# Trackerv4.net
KiCad netlist of a schematic drawn in EAGLE
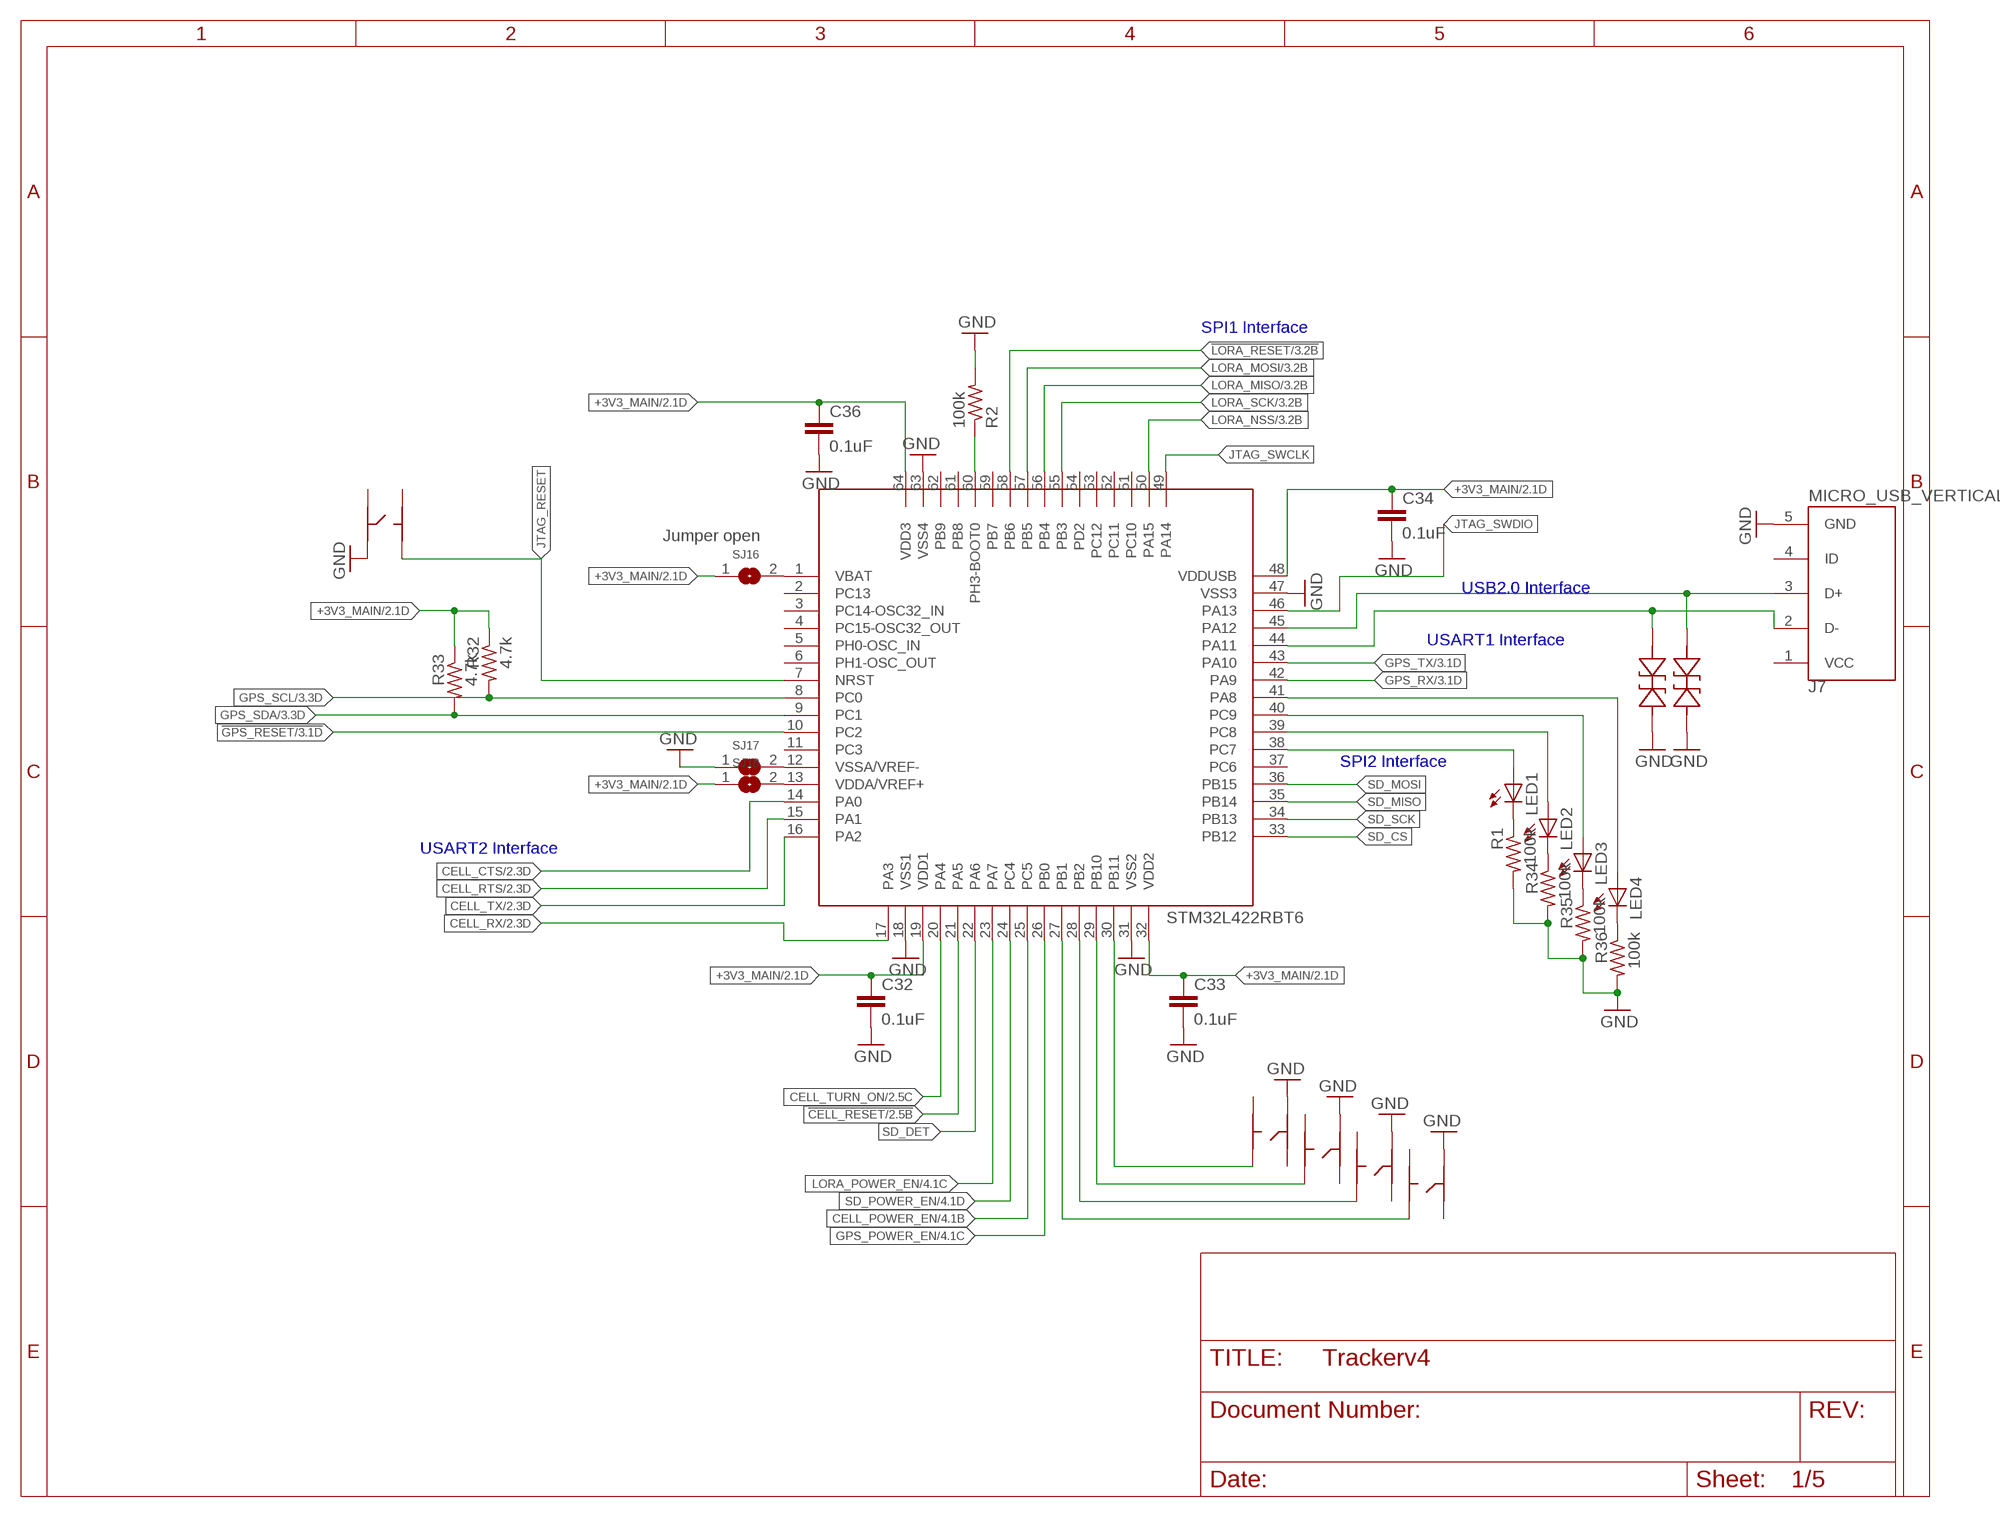
[diagram p0: schematic, sheet 1]
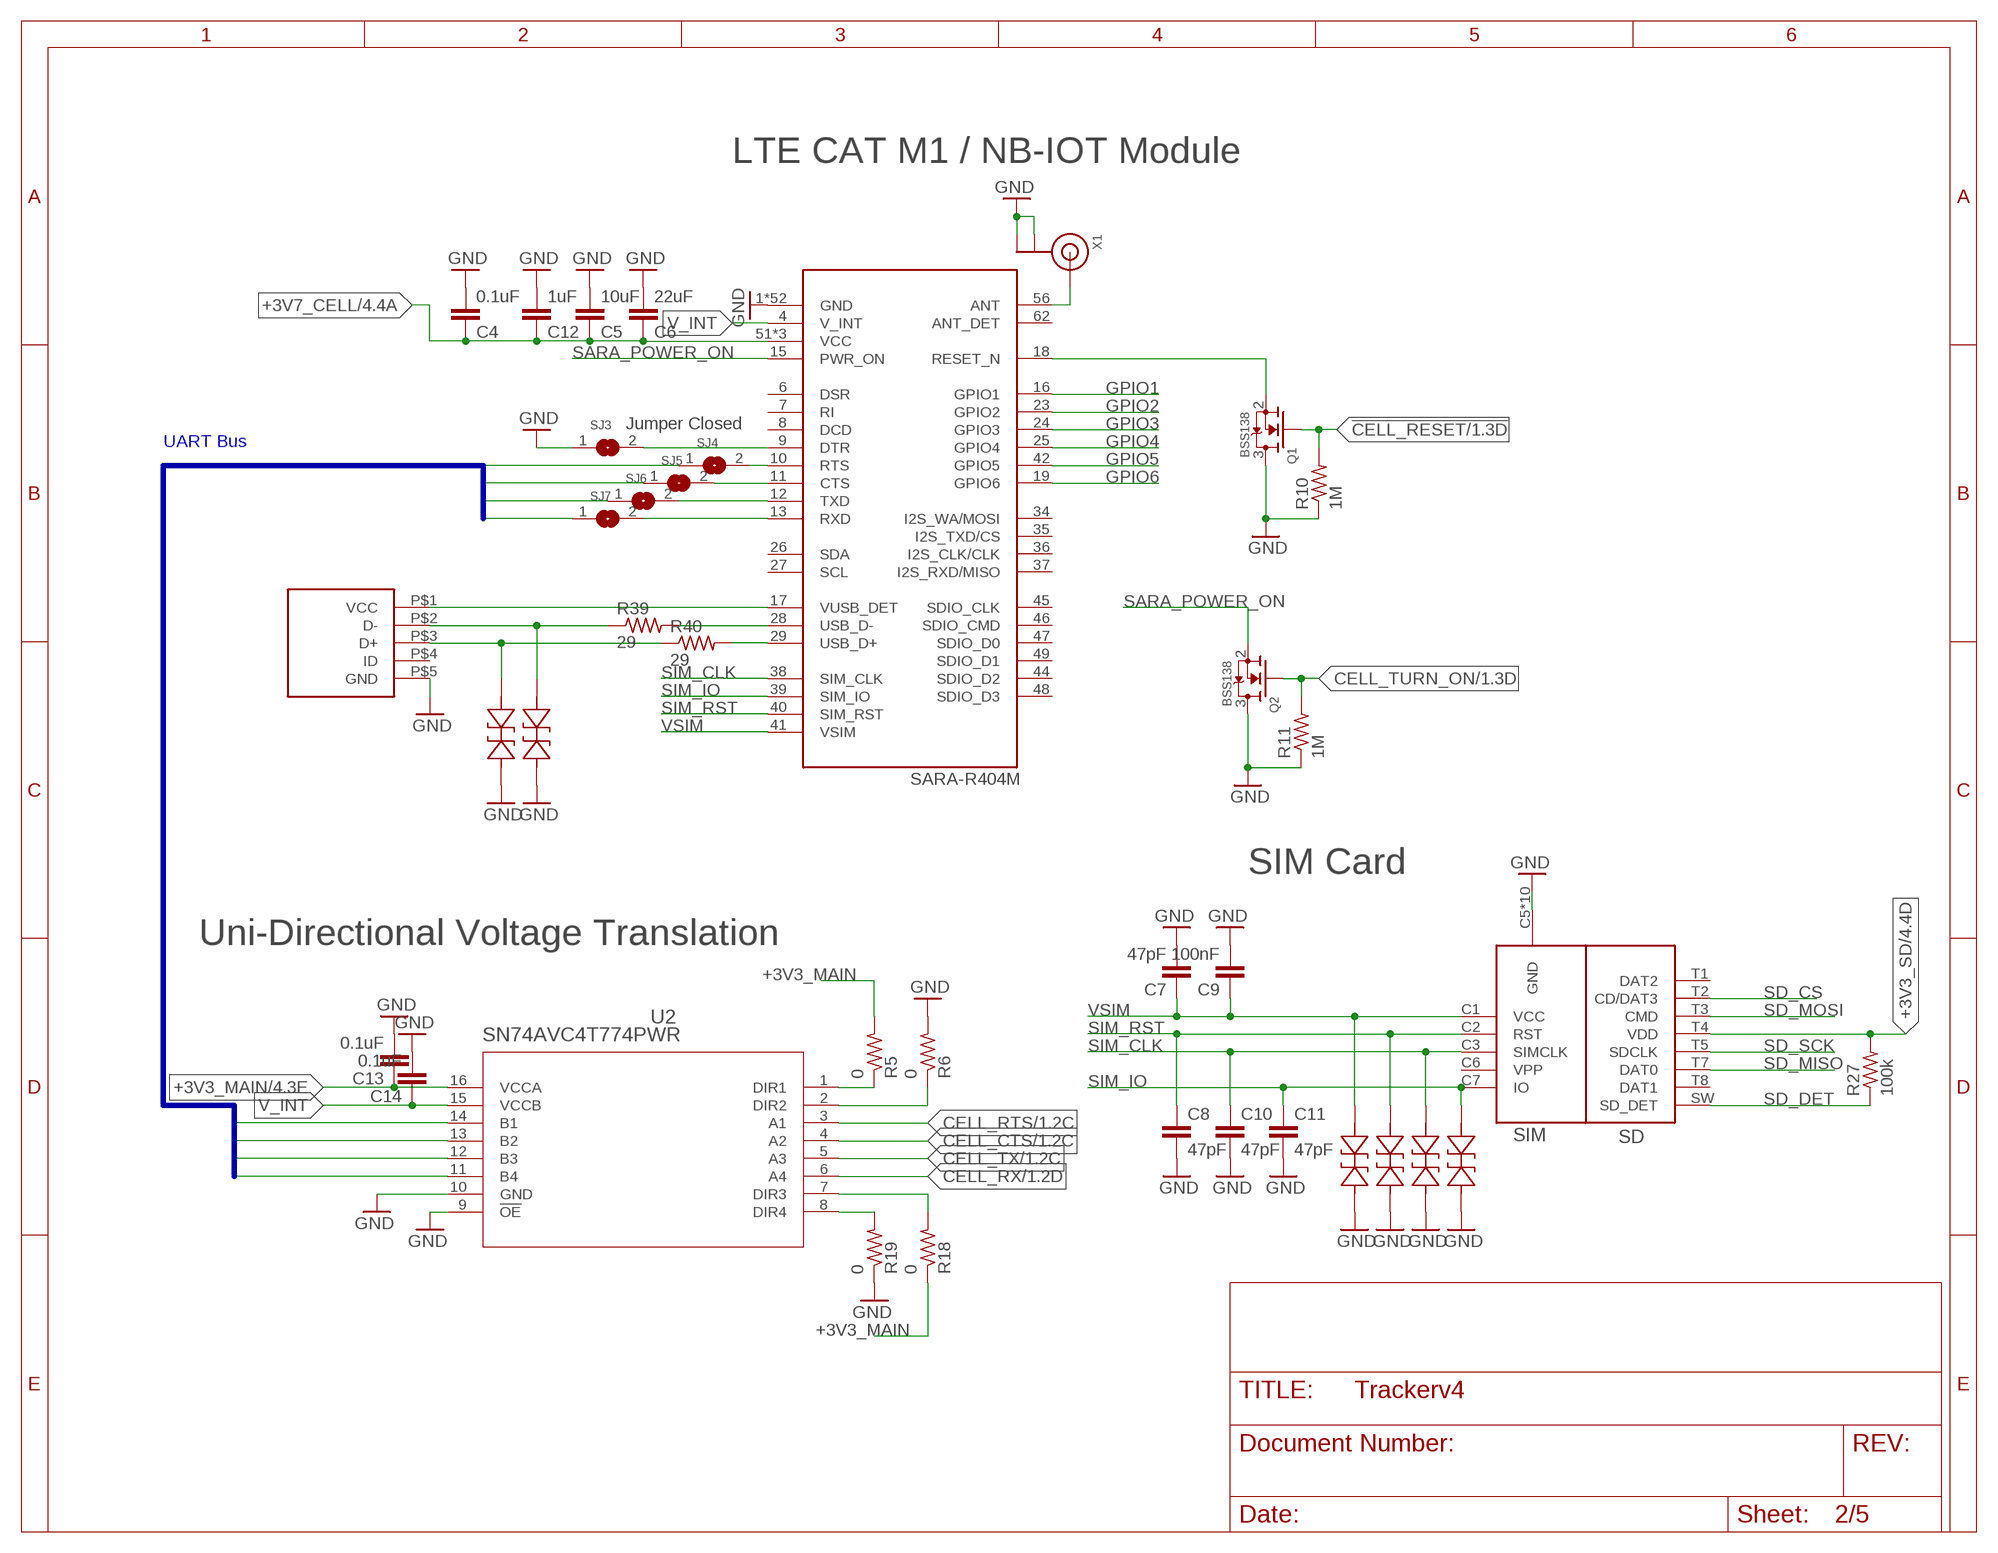
[diagram p1: schematic, sheet 2]
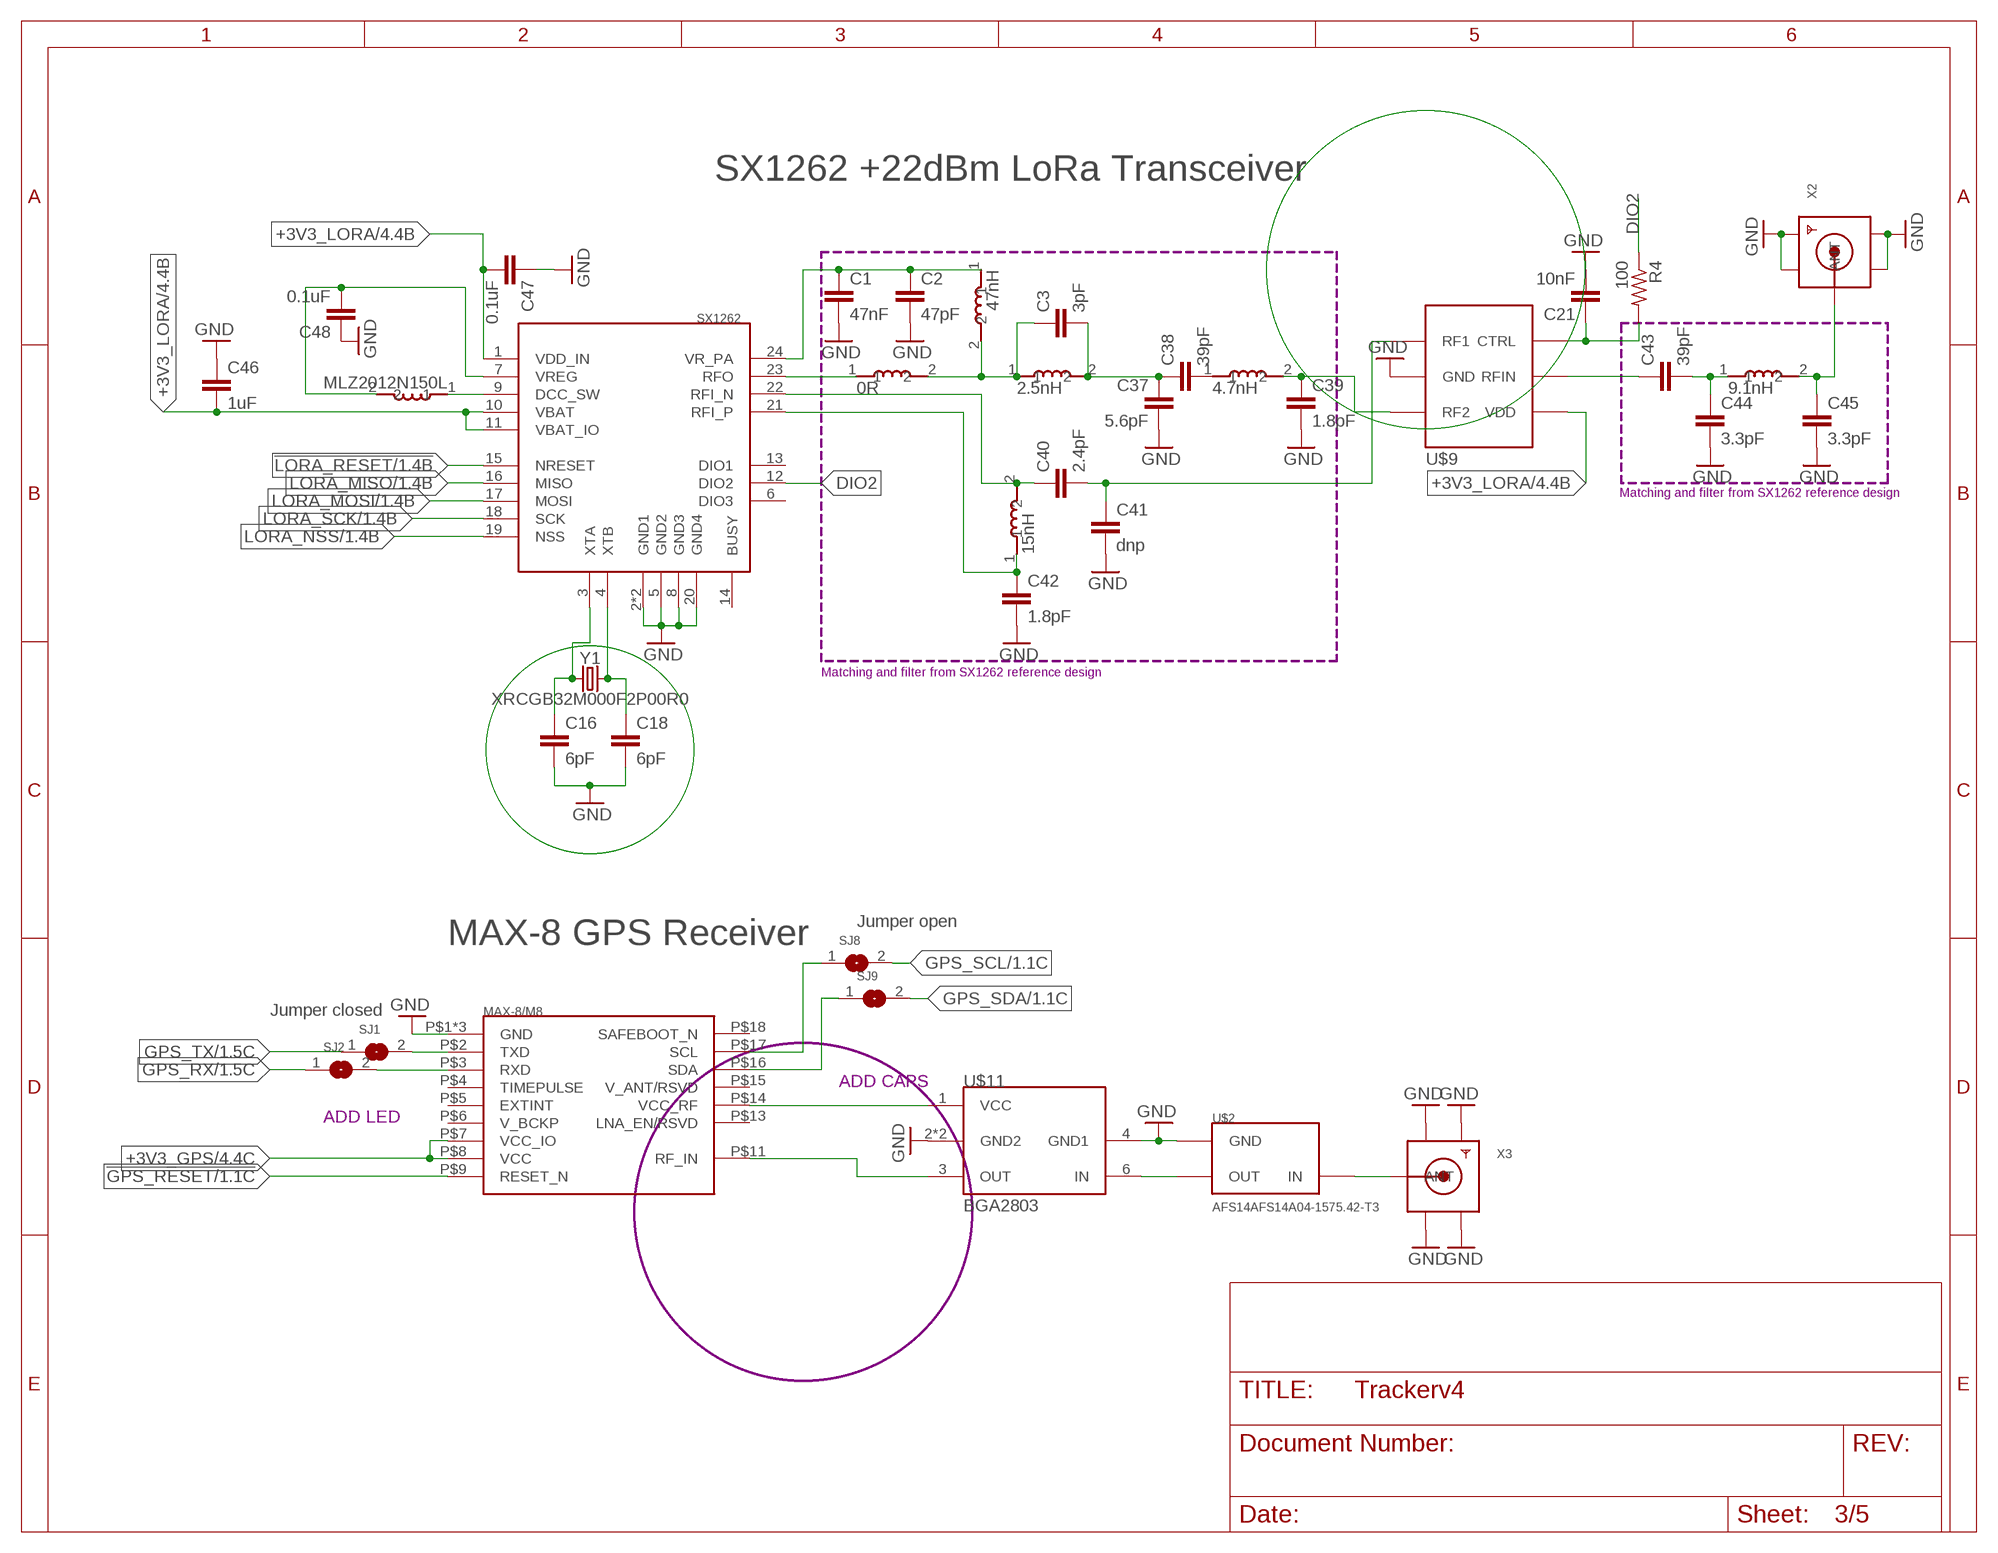
[diagram p2: schematic, sheet 3]
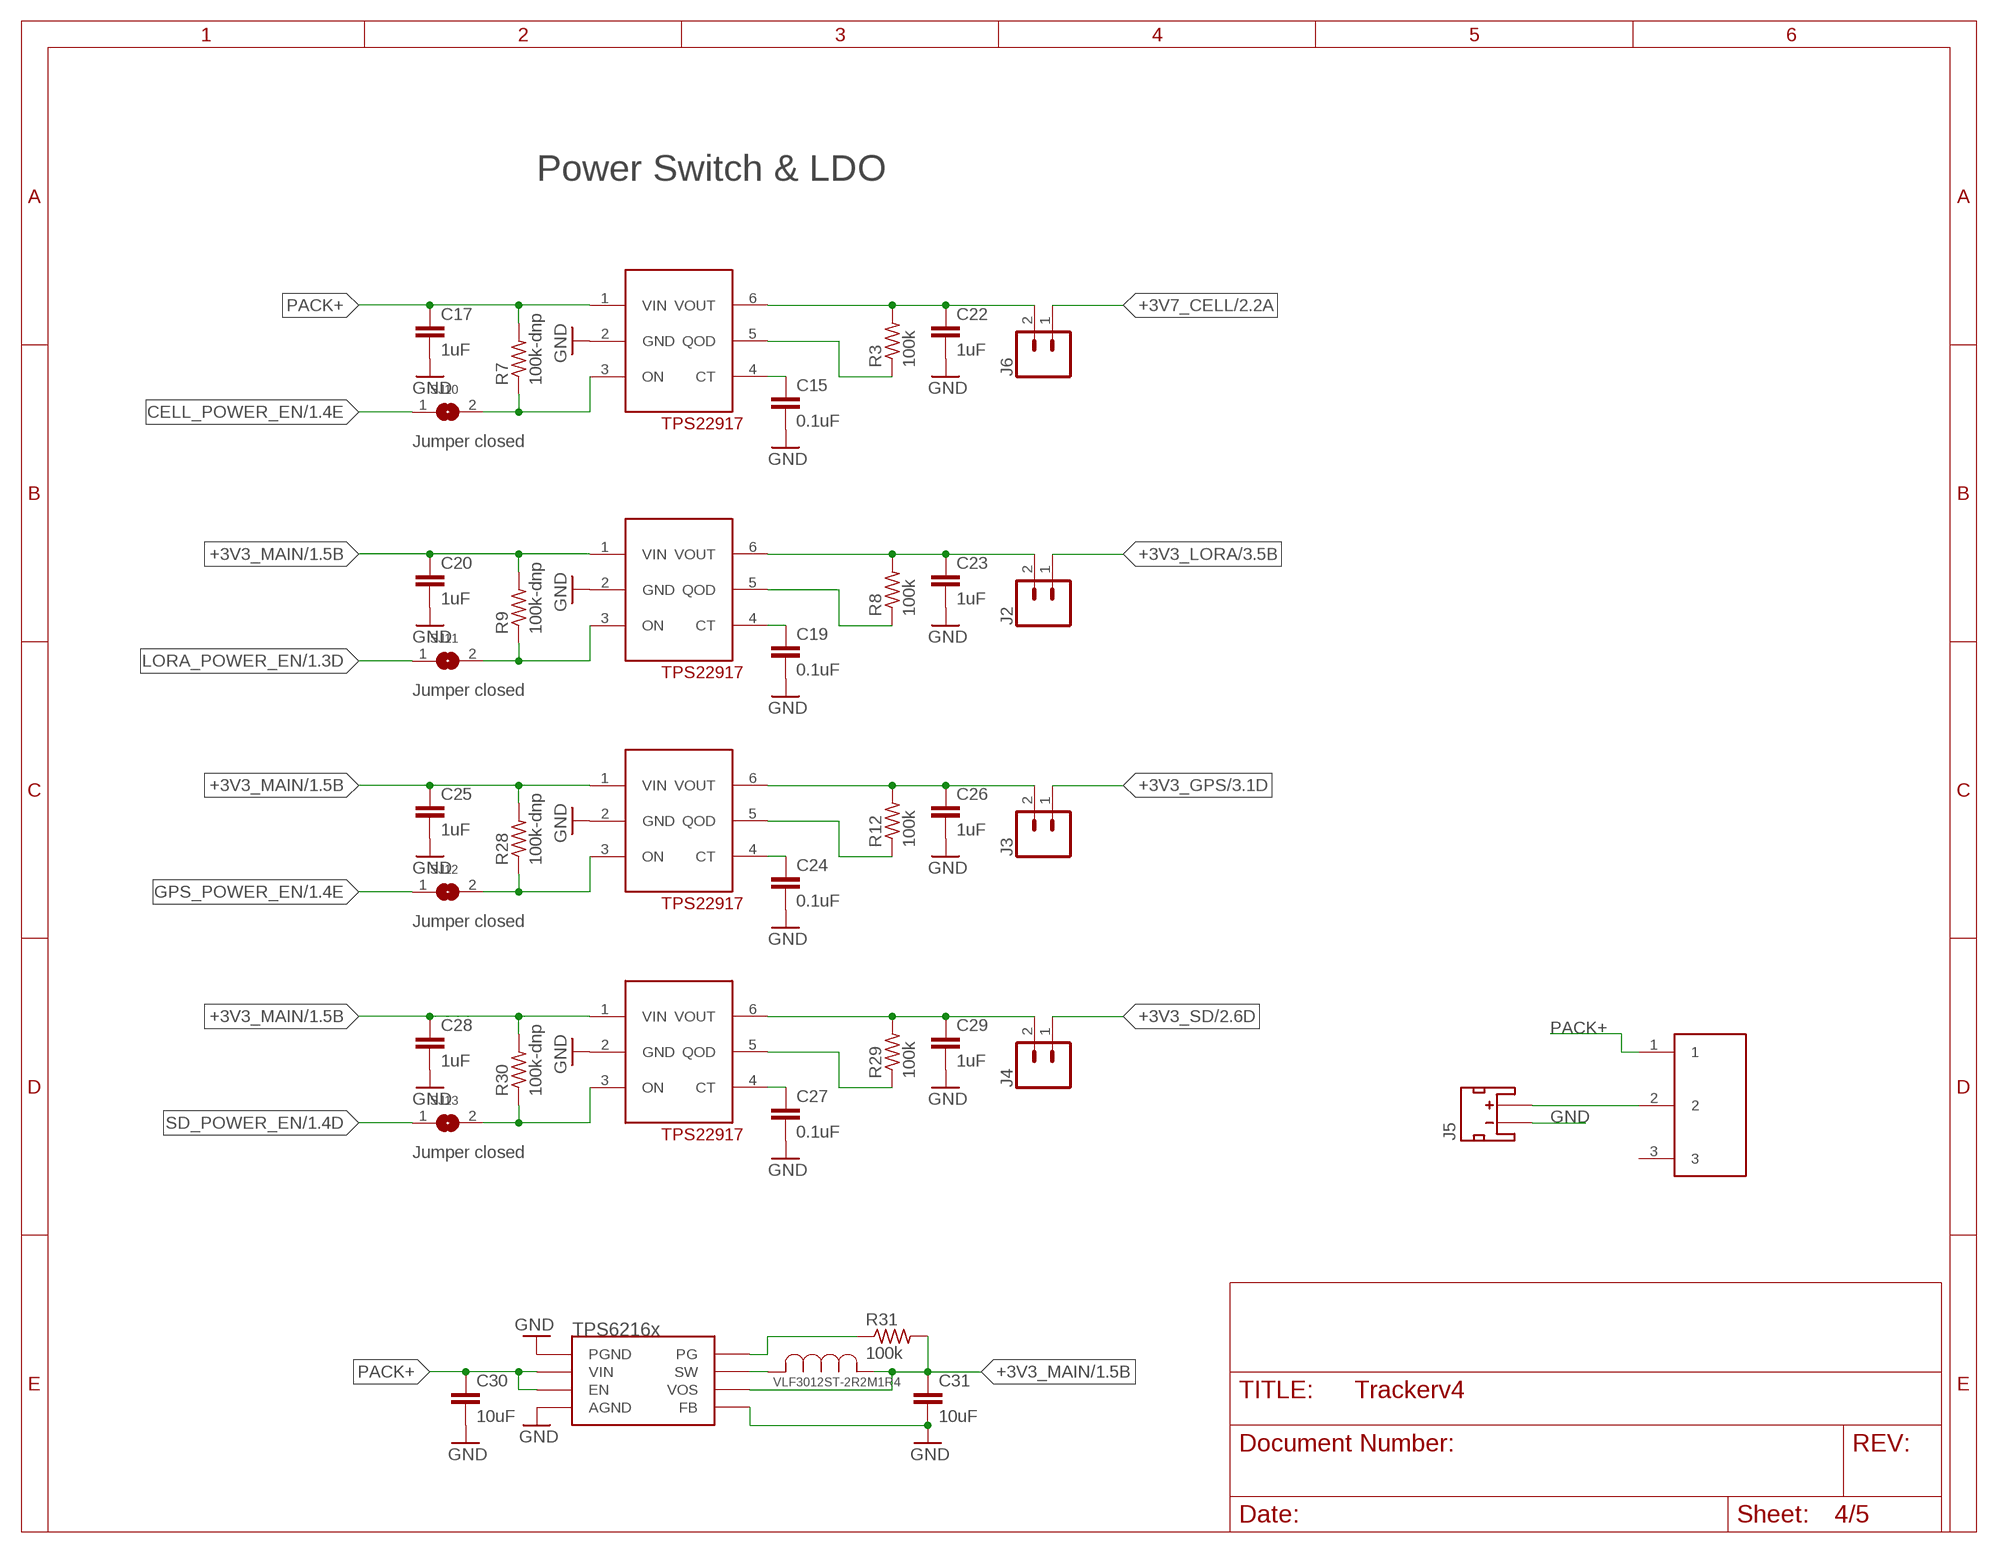
[diagram p3: schematic, sheet 4]
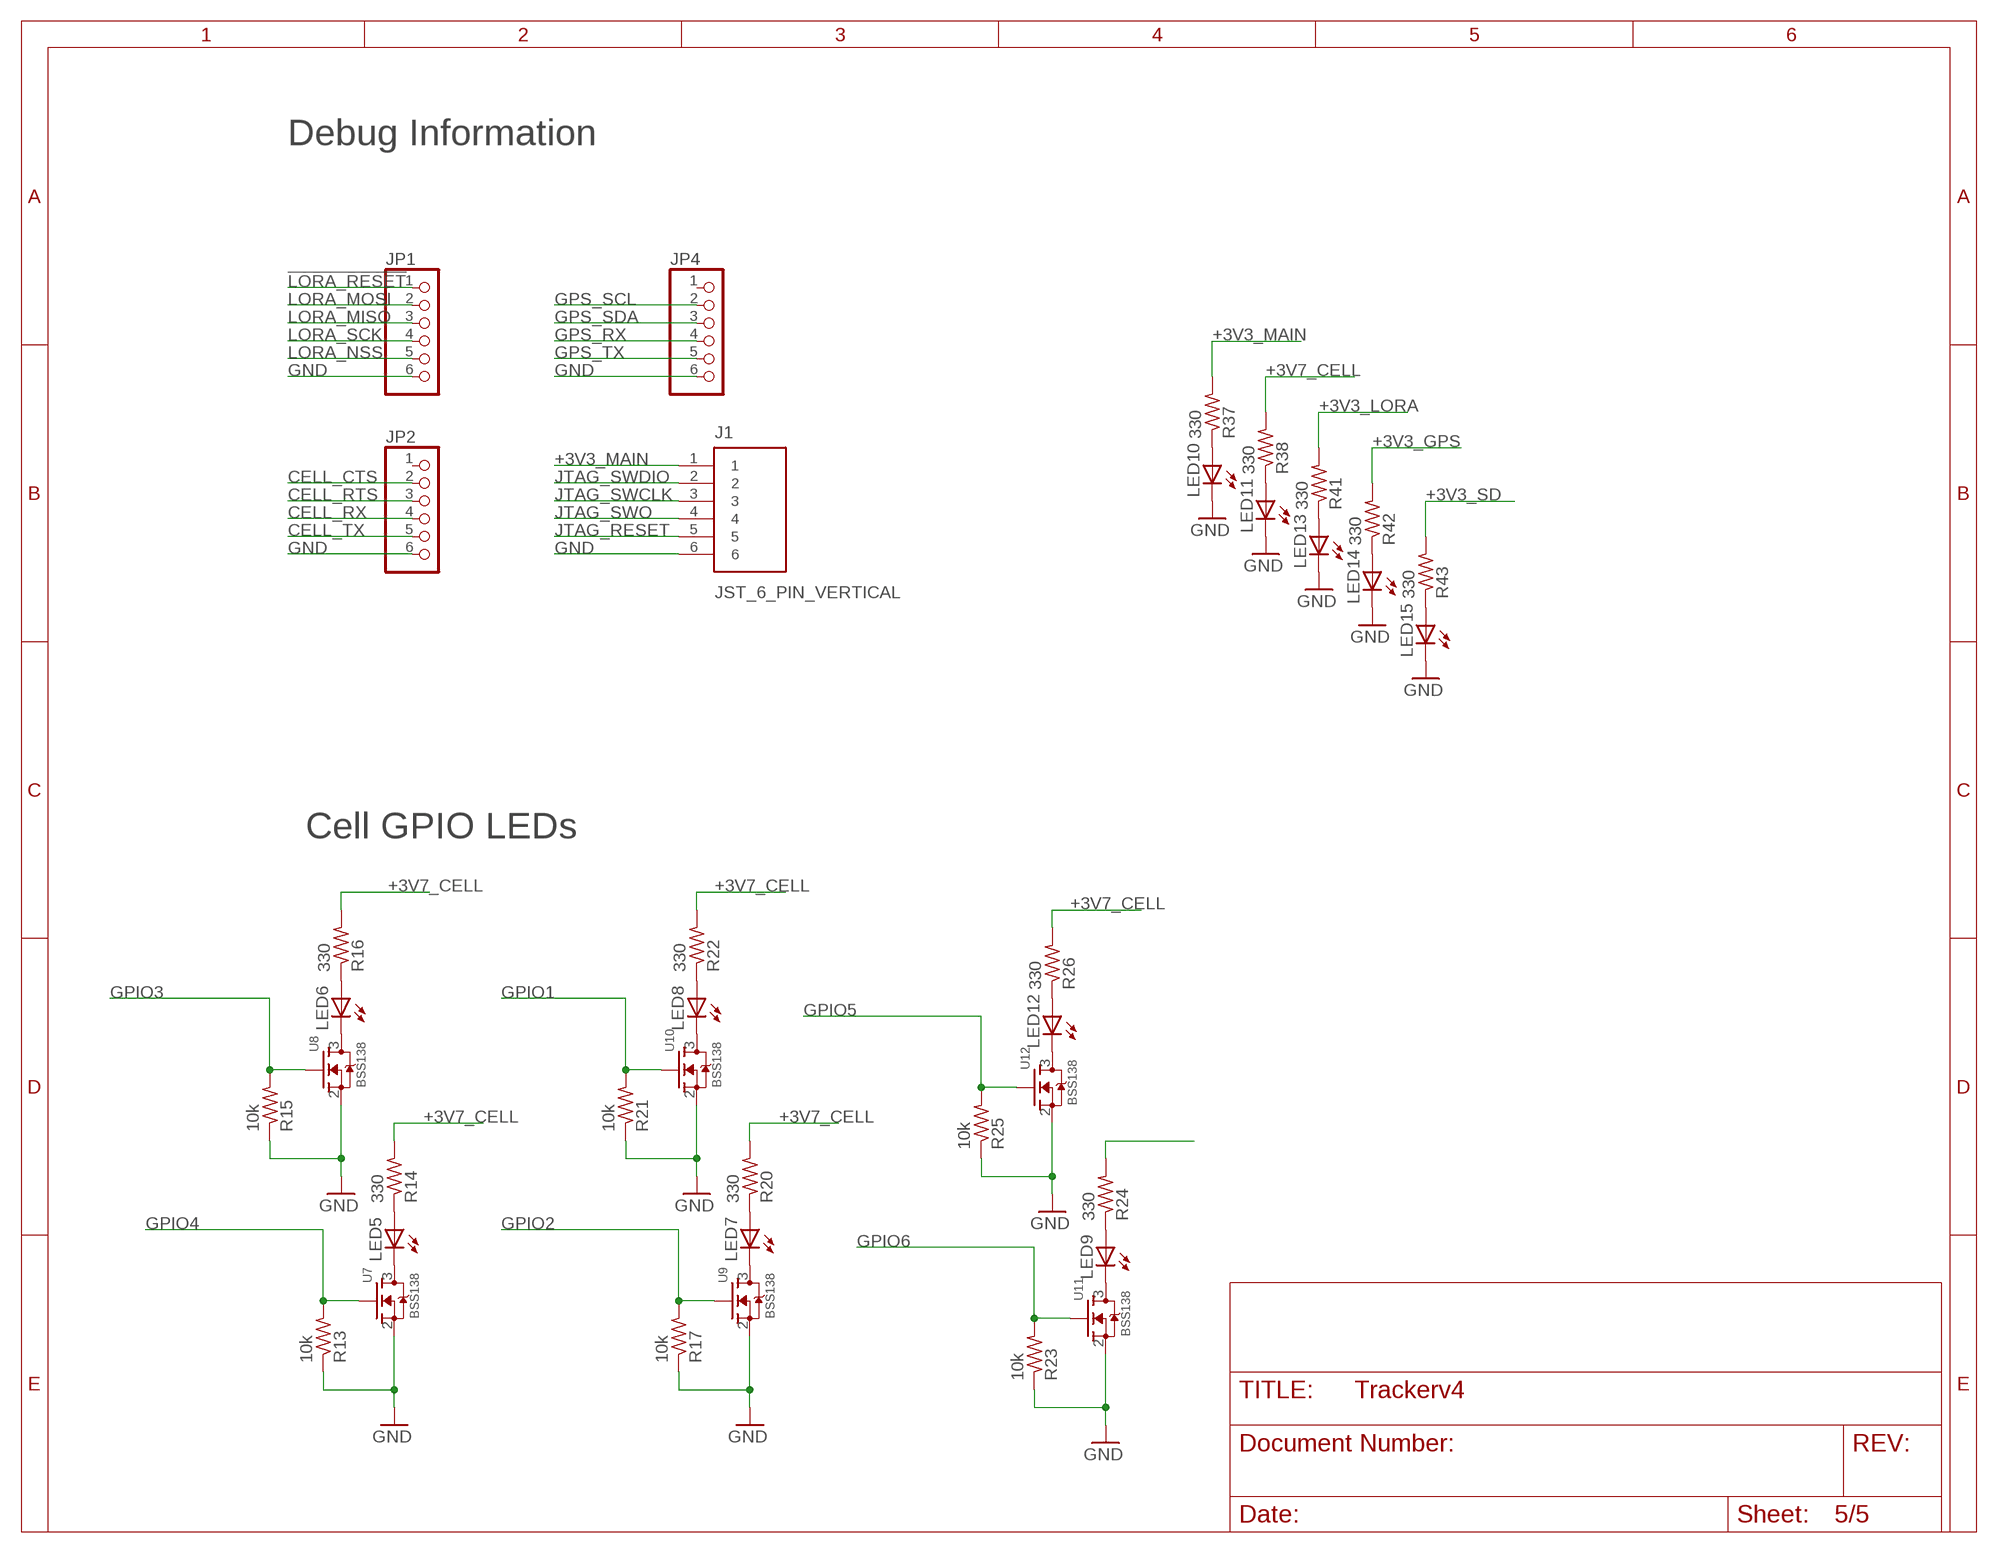
[diagram p4: schematic, sheet 5]

(export (version "E")
  (design (tool "Eeschema 10.0.6"))
  (components
    (comp (ref "J1")
      (value "JST_6_PIN_VERTICAL")
      (footprint "eagle-import:JST-6-SMD-VERT-1.0MM")
      (libsource (lib "eagle-import") (part "JST_6_PIN_VERTICAL"))
    )
    (comp (ref "JP1")
      (value "PINHD-1X6")
      (footprint "eagle-import:1X06")
      (libsource (lib "eagle-import") (part "PINHD-1X6"))
    )
    (comp (ref "JP2")
      (value "PINHD-1X6")
      (footprint "eagle-import:1X06")
      (libsource (lib "eagle-import") (part "PINHD-1X6"))
    )
    (comp (ref "JP4")
      (value "PINHD-1X6")
      (footprint "eagle-import:1X06")
      (libsource (lib "eagle-import") (part "PINHD-1X6"))
    )
    (comp (ref "LED5")
      (value "LEDCHIPLED_0603")
      (footprint "eagle-import:CHIPLED_0603")
      (libsource (lib "eagle-import") (part "LEDCHIPLED_0603"))
    )
    (comp (ref "LED6")
      (value "LEDCHIPLED_0603")
      (footprint "eagle-import:CHIPLED_0603")
      (libsource (lib "eagle-import") (part "LEDCHIPLED_0603"))
    )
    (comp (ref "LED7")
      (value "LEDCHIPLED_0603")
      (footprint "eagle-import:CHIPLED_0603")
      (libsource (lib "eagle-import") (part "LEDCHIPLED_0603"))
    )
    (comp (ref "LED8")
      (value "LEDCHIPLED_0603")
      (footprint "eagle-import:CHIPLED_0603")
      (libsource (lib "eagle-import") (part "LEDCHIPLED_0603"))
    )
    (comp (ref "LED9")
      (value "LEDCHIPLED_0603")
      (footprint "eagle-import:CHIPLED_0603")
      (libsource (lib "eagle-import") (part "LEDCHIPLED_0603"))
    )
    (comp (ref "LED10")
      (value "LEDCHIPLED_0603")
      (footprint "eagle-import:CHIPLED_0603")
      (libsource (lib "eagle-import") (part "LEDCHIPLED_0603"))
    )
    (comp (ref "LED11")
      (value "LEDCHIPLED_0603")
      (footprint "eagle-import:CHIPLED_0603")
      (libsource (lib "eagle-import") (part "LEDCHIPLED_0603"))
    )
    (comp (ref "LED12")
      (value "LEDCHIPLED_0603")
      (footprint "eagle-import:CHIPLED_0603")
      (libsource (lib "eagle-import") (part "LEDCHIPLED_0603"))
    )
    (comp (ref "LED13")
      (value "LEDCHIPLED_0603")
      (footprint "eagle-import:CHIPLED_0603")
      (libsource (lib "eagle-import") (part "LEDCHIPLED_0603"))
    )
    (comp (ref "LED14")
      (value "LEDCHIPLED_0603")
      (footprint "eagle-import:CHIPLED_0603")
      (libsource (lib "eagle-import") (part "LEDCHIPLED_0603"))
    )
    (comp (ref "LED15")
      (value "LEDCHIPLED_0603")
      (footprint "eagle-import:CHIPLED_0603")
      (libsource (lib "eagle-import") (part "LEDCHIPLED_0603"))
    )
    (comp (ref "R13")
      (value "10k")
      (footprint "eagle-import:R0402")
      (libsource (lib "eagle-import") (part "R-US_R0402"))
    )
    (comp (ref "R14")
      (value "330")
      (footprint "eagle-import:R0402")
      (libsource (lib "eagle-import") (part "R-US_R0402"))
    )
    (comp (ref "R15")
      (value "10k")
      (footprint "eagle-import:R0402")
      (libsource (lib "eagle-import") (part "R-US_R0402"))
    )
    (comp (ref "R16")
      (value "330")
      (footprint "eagle-import:R0402")
      (libsource (lib "eagle-import") (part "R-US_R0402"))
    )
    (comp (ref "R17")
      (value "10k")
      (footprint "eagle-import:R0402")
      (libsource (lib "eagle-import") (part "R-US_R0402"))
    )
    (comp (ref "R20")
      (value "330")
      (footprint "eagle-import:R0402")
      (libsource (lib "eagle-import") (part "R-US_R0402"))
    )
    (comp (ref "R21")
      (value "10k")
      (footprint "eagle-import:R0402")
      (libsource (lib "eagle-import") (part "R-US_R0402"))
    )
    (comp (ref "R22")
      (value "330")
      (footprint "eagle-import:R0402")
      (libsource (lib "eagle-import") (part "R-US_R0402"))
    )
    (comp (ref "R23")
      (value "10k")
      (footprint "eagle-import:R0402")
      (libsource (lib "eagle-import") (part "R-US_R0402"))
    )
    (comp (ref "R24")
      (value "330")
      (footprint "eagle-import:R0402")
      (libsource (lib "eagle-import") (part "R-US_R0402"))
    )
    (comp (ref "R25")
      (value "10k")
      (footprint "eagle-import:R0402")
      (libsource (lib "eagle-import") (part "R-US_R0402"))
    )
    (comp (ref "R26")
      (value "330")
      (footprint "eagle-import:R0402")
      (libsource (lib "eagle-import") (part "R-US_R0402"))
    )
    (comp (ref "R37")
      (value "330")
      (footprint "eagle-import:R0402")
      (libsource (lib "eagle-import") (part "R-US_R0402"))
    )
    (comp (ref "R38")
      (value "330")
      (footprint "eagle-import:R0402")
      (libsource (lib "eagle-import") (part "R-US_R0402"))
    )
    (comp (ref "R41")
      (value "330")
      (footprint "eagle-import:R0402")
      (libsource (lib "eagle-import") (part "R-US_R0402"))
    )
    (comp (ref "R42")
      (value "330")
      (footprint "eagle-import:R0402")
      (libsource (lib "eagle-import") (part "R-US_R0402"))
    )
    (comp (ref "R43")
      (value "330")
      (footprint "eagle-import:R0402")
      (libsource (lib "eagle-import") (part "R-US_R0402"))
    )
    (comp (ref "U7")
      (value "BSS138")
      (footprint "eagle-import:SOT23-3")
      (libsource (lib "eagle-import") (part "BSS138"))
    )
    (comp (ref "U8")
      (value "BSS138")
      (footprint "eagle-import:SOT23-3")
      (libsource (lib "eagle-import") (part "BSS138"))
    )
    (comp (ref "U9")
      (value "BSS138")
      (footprint "eagle-import:SOT23-3")
      (libsource (lib "eagle-import") (part "BSS138"))
    )
    (comp (ref "U10")
      (value "BSS138")
      (footprint "eagle-import:SOT23-3")
      (libsource (lib "eagle-import") (part "BSS138"))
    )
    (comp (ref "U11")
      (value "BSS138")
      (footprint "eagle-import:SOT23-3")
      (libsource (lib "eagle-import") (part "BSS138"))
    )
    (comp (ref "U12")
      (value "BSS138")
      (footprint "eagle-import:SOT23-3")
      (libsource (lib "eagle-import") (part "BSS138"))
    )
    (comp (ref "C1")
      (value "47nF")
      (footprint "eagle-import:C0402")
      (libsource (lib "eagle-import") (part "C-EUC0402"))
    )
    (comp (ref "C2")
      (value "47pF")
      (footprint "eagle-import:C0402")
      (libsource (lib "eagle-import") (part "C-EUC0402"))
    )
    (comp (ref "C3")
      (value "3pF")
      (footprint "eagle-import:C0402")
      (libsource (lib "eagle-import") (part "C-EUC0402"))
    )
    (comp (ref "C16")
      (value "6pF")
      (footprint "eagle-import:C0402")
      (libsource (lib "eagle-import") (part "C-EUC0402"))
    )
    (comp (ref "C18")
      (value "6pF")
      (footprint "eagle-import:C0402")
      (libsource (lib "eagle-import") (part "C-EUC0402"))
    )
    (comp (ref "C21")
      (value "10nF")
      (footprint "eagle-import:C0402")
      (libsource (lib "eagle-import") (part "C-EUC0402"))
    )
    (comp (ref "C37")
      (value "5.6pF")
      (footprint "eagle-import:C0402")
      (libsource (lib "eagle-import") (part "C-EUC0402"))
    )
    (comp (ref "C38")
      (value "39pF")
      (footprint "eagle-import:C0402")
      (libsource (lib "eagle-import") (part "C-EUC0402"))
    )
    (comp (ref "C39")
      (value "1.8pF")
      (footprint "eagle-import:C0402")
      (libsource (lib "eagle-import") (part "C-EUC0402"))
    )
    (comp (ref "C40")
      (value "2.4pF")
      (footprint "eagle-import:C0402")
      (libsource (lib "eagle-import") (part "C-EUC0402"))
    )
    (comp (ref "C41")
      (value "dnp")
      (footprint "eagle-import:C0402")
      (libsource (lib "eagle-import") (part "C-EUC0402"))
    )
    (comp (ref "C42")
      (value "1.8pF")
      (footprint "eagle-import:C0402")
      (libsource (lib "eagle-import") (part "C-EUC0402"))
    )
    (comp (ref "C43")
      (value "39pF")
      (footprint "eagle-import:C0402")
      (libsource (lib "eagle-import") (part "C-EUC0402"))
    )
    (comp (ref "C44")
      (value "3.3pF")
      (footprint "eagle-import:C0402")
      (libsource (lib "eagle-import") (part "C-EUC0402"))
    )
    (comp (ref "C45")
      (value "3.3pF")
      (footprint "eagle-import:C0402")
      (libsource (lib "eagle-import") (part "C-EUC0402"))
    )
    (comp (ref "C46")
      (value "1uF")
      (footprint "eagle-import:C0603")
      (libsource (lib "eagle-import") (part "C-EUC0603"))
    )
    (comp (ref "C47")
      (value "0.1uF")
      (footprint "eagle-import:C0402")
      (libsource (lib "eagle-import") (part "C-EUC0402"))
    )
    (comp (ref "C48")
      (value "0.1uF")
      (footprint "eagle-import:C0402")
      (libsource (lib "eagle-import") (part "C-EUC0402"))
    )
    (comp (ref "R4")
      (value "100")
      (footprint "eagle-import:R0402")
      (libsource (lib "eagle-import") (part "R-US_R0402"))
    )
    (comp (ref "SJ1")
      (value "SOLDERJUMPERCLOSED")
      (footprint "eagle-import:SOLDERJUMPER_CLOSEDWIRE")
      (libsource (lib "eagle-import") (part "SOLDERJUMPERCLOSED"))
    )
    (comp (ref "SJ2")
      (value "SOLDERJUMPERCLOSED")
      (footprint "eagle-import:SOLDERJUMPER_CLOSEDWIRE")
      (libsource (lib "eagle-import") (part "SOLDERJUMPERCLOSED"))
    )
    (comp (ref "SJ8")
      (value "SOLDERJUMPERREFLOW")
      (footprint "eagle-import:SOLDERJUMPER_REFLOW")
      (libsource (lib "eagle-import") (part "SOLDERJUMPERREFLOW"))
    )
    (comp (ref "SJ9")
      (value "SOLDERJUMPERREFLOW")
      (footprint "eagle-import:SOLDERJUMPER_REFLOW")
      (libsource (lib "eagle-import") (part "SOLDERJUMPERREFLOW"))
    )
    (comp (ref "U$2")
      (value "AFS14AFS14A04-1575.42-T3")
      (footprint "eagle-import:AFS14")
      (libsource (lib "eagle-import") (part "AFS14AFS14A04-1575.42-T3"))
    )
    (comp (ref "U$3")
      (value "MLZ2012N150L")
      (footprint "eagle-import:C0805")
      (libsource (lib "eagle-import") (part "INDUCTOR0805"))
    )
    (comp (ref "U$7")
      (value "SX1262")
      (footprint "eagle-import:QFN50P400X400X100-25T260")
      (libsource (lib "eagle-import") (part "SX1262"))
    )
    (comp (ref "U$8")
      (value "MAX-8/M8")
      (footprint "eagle-import:MAX-8-M8")
      (libsource (lib "eagle-import") (part "MAX-8/M8"))
    )
    (comp (ref "U$9")
      (value "BGS12SN6E6327XTSA1")
      (footprint "eagle-import:TSNP-6-8")
      (libsource (lib "eagle-import") (part "BGS12SN6E6327XTSA1"))
    )
    (comp (ref "U$10")
      (value "47nH")
      (footprint "eagle-import:0402")
      (libsource (lib "eagle-import") (part "INDUCTOR0402"))
    )
    (comp (ref "U$11")
      (value "BGA2803")
      (footprint "eagle-import:SOT363_6SOIC")
      (libsource (lib "eagle-import") (part "BGA2803"))
    )
    (comp (ref "U$12")
      (value "2.5nH")
      (footprint "eagle-import:0402")
      (libsource (lib "eagle-import") (part "INDUCTOR0402"))
    )
    (comp (ref "U$13")
      (value "4.7nH")
      (footprint "eagle-import:0402")
      (libsource (lib "eagle-import") (part "INDUCTOR0402"))
    )
    (comp (ref "U$14")
      (value "15nH")
      (footprint "eagle-import:0402")
      (libsource (lib "eagle-import") (part "INDUCTOR0402"))
    )
    (comp (ref "U$15")
      (value "9.1nH")
      (footprint "eagle-import:0402")
      (libsource (lib "eagle-import") (part "INDUCTOR0402"))
    )
    (comp (ref "U$16")
      (value "0R")
      (footprint "eagle-import:0402")
      (libsource (lib "eagle-import") (part "INDUCTOR0402"))
    )
    (comp (ref "X2")
      (value "SMACONNECTOR_EDGE")
      (footprint "eagle-import:SMA_EDGELAUNCH")
      (libsource (lib "eagle-import") (part "SMACONNECTOR_EDGE"))
    )
    (comp (ref "X3")
      (value "SMACONNECTOR_EDGE_UFL")
      (footprint "eagle-import:SMA_EDGELAUNCH_UFL")
      (libsource (lib "eagle-import") (part "SMACONNECTOR_EDGE_UFL"))
    )
    (comp (ref "Y1")
      (value "XRCGB32M000F2P00R0")
      (footprint "eagle-import:CRYSTAL-SMD-2.0X1.6MM")
      (libsource (lib "eagle-import") (part "CRYSTAL-32MHZ-SMD-2.0X1.6MM"))
    )
    (comp (ref "C15")
      (value "0.1uF")
      (footprint "eagle-import:C0402")
      (libsource (lib "eagle-import") (part "C-EUC0402"))
    )
    (comp (ref "C17")
      (value "1uF")
      (footprint "eagle-import:C0402")
      (libsource (lib "eagle-import") (part "C-EUC0402"))
    )
    (comp (ref "C19")
      (value "0.1uF")
      (footprint "eagle-import:C0402")
      (libsource (lib "eagle-import") (part "C-EUC0402"))
    )
    (comp (ref "C20")
      (value "1uF")
      (footprint "eagle-import:C0402")
      (libsource (lib "eagle-import") (part "C-EUC0402"))
    )
    (comp (ref "C22")
      (value "1uF")
      (footprint "eagle-import:C0402")
      (libsource (lib "eagle-import") (part "C-EUC0402"))
    )
    (comp (ref "C23")
      (value "1uF")
      (footprint "eagle-import:C0402")
      (libsource (lib "eagle-import") (part "C-EUC0402"))
    )
    (comp (ref "C24")
      (value "0.1uF")
      (footprint "eagle-import:C0402")
      (libsource (lib "eagle-import") (part "C-EUC0402"))
    )
    (comp (ref "C25")
      (value "1uF")
      (footprint "eagle-import:C0402")
      (libsource (lib "eagle-import") (part "C-EUC0402"))
    )
    (comp (ref "C26")
      (value "1uF")
      (footprint "eagle-import:C0402")
      (libsource (lib "eagle-import") (part "C-EUC0402"))
    )
    (comp (ref "C27")
      (value "0.1uF")
      (footprint "eagle-import:C0402")
      (libsource (lib "eagle-import") (part "C-EUC0402"))
    )
    (comp (ref "C28")
      (value "1uF")
      (footprint "eagle-import:C0402")
      (libsource (lib "eagle-import") (part "C-EUC0402"))
    )
    (comp (ref "C29")
      (value "1uF")
      (footprint "eagle-import:C0402")
      (libsource (lib "eagle-import") (part "C-EUC0402"))
    )
    (comp (ref "C30")
      (value "10uF")
      (footprint "eagle-import:C0805")
      (libsource (lib "eagle-import") (part "C-EUC0805"))
    )
    (comp (ref "C31")
      (value "10uF")
      (footprint "eagle-import:C0805")
      (libsource (lib "eagle-import") (part "C-EUC0805"))
    )
    (comp (ref "J2")
      (value "CONN_02")
      (footprint "eagle-import:1X02")
      (libsource (lib "eagle-import") (part "CONN_02"))
    )
    (comp (ref "J3")
      (value "CONN_02")
      (footprint "eagle-import:1X02")
      (libsource (lib "eagle-import") (part "CONN_02"))
    )
    (comp (ref "J4")
      (value "CONN_02")
      (footprint "eagle-import:1X02")
      (libsource (lib "eagle-import") (part "CONN_02"))
    )
    (comp (ref "J5")
      (value "JST_2MM_MALE")
      (footprint "eagle-import:JST-2-SMD")
      (libsource (lib "eagle-import") (part "JST_2MM_MALE"))
    )
    (comp (ref "J6")
      (value "CONN_02")
      (footprint "eagle-import:1X02")
      (libsource (lib "eagle-import") (part "CONN_02"))
    )
    (comp (ref "R3")
      (value "100k")
      (footprint "eagle-import:R0402")
      (libsource (lib "eagle-import") (part "R-US_R0402"))
    )
    (comp (ref "R7")
      (value "100k-dnp")
      (footprint "eagle-import:R0402")
      (libsource (lib "eagle-import") (part "R-US_R0402"))
    )
    (comp (ref "R8")
      (value "100k")
      (footprint "eagle-import:R0402")
      (libsource (lib "eagle-import") (part "R-US_R0402"))
    )
    (comp (ref "R9")
      (value "100k-dnp")
      (footprint "eagle-import:R0402")
      (libsource (lib "eagle-import") (part "R-US_R0402"))
    )
    (comp (ref "R12")
      (value "100k")
      (footprint "eagle-import:R0402")
      (libsource (lib "eagle-import") (part "R-US_R0402"))
    )
    (comp (ref "R28")
      (value "100k-dnp")
      (footprint "eagle-import:R0402")
      (libsource (lib "eagle-import") (part "R-US_R0402"))
    )
    (comp (ref "R29")
      (value "100k")
      (footprint "eagle-import:R0402")
      (libsource (lib "eagle-import") (part "R-US_R0402"))
    )
    (comp (ref "R30")
      (value "100k-dnp")
      (footprint "eagle-import:R0402")
      (libsource (lib "eagle-import") (part "R-US_R0402"))
    )
    (comp (ref "R31")
      (value "100k")
      (footprint "eagle-import:R0402")
      (libsource (lib "eagle-import") (part "R-US_R0402"))
    )
    (comp (ref "SJ10")
      (value "SOLDERJUMPERCLOSED")
      (footprint "eagle-import:SOLDERJUMPER_CLOSEDWIRE")
      (libsource (lib "eagle-import") (part "SOLDERJUMPERCLOSED"))
    )
    (comp (ref "SJ11")
      (value "SOLDERJUMPERCLOSED")
      (footprint "eagle-import:SOLDERJUMPER_CLOSEDWIRE")
      (libsource (lib "eagle-import") (part "SOLDERJUMPERCLOSED"))
    )
    (comp (ref "SJ12")
      (value "SOLDERJUMPERCLOSED")
      (footprint "eagle-import:SOLDERJUMPER_CLOSEDWIRE")
      (libsource (lib "eagle-import") (part "SOLDERJUMPERCLOSED"))
    )
    (comp (ref "SJ13")
      (value "SOLDERJUMPERCLOSED")
      (footprint "eagle-import:SOLDERJUMPER_CLOSEDWIRE")
      (libsource (lib "eagle-import") (part "SOLDERJUMPERCLOSED"))
    )
    (comp (ref "U$4")
      (value "VLF3012ST-2R2M1R4")
      (footprint "eagle-import:IND_3010")
      (libsource (lib "eagle-import") (part "VLF3012ST-2R2M1R4"))
    )
    (comp (ref "U$17")
      (value "SPDT_THRU")
      (footprint "eagle-import:SPDT_THRU")
      (libsource (lib "eagle-import") (part "SPDT_THRU"))
    )
    (comp (ref "U1")
      (value "TPS22917")
      (footprint "eagle-import:SOT23-6")
      (libsource (lib "eagle-import") (part "TPS22917"))
    )
    (comp (ref "U3")
      (value "TPS22917")
      (footprint "eagle-import:SOT23-6")
      (libsource (lib "eagle-import") (part "TPS22917"))
    )
    (comp (ref "U4")
      (value "TPS22917")
      (footprint "eagle-import:SOT23-6")
      (libsource (lib "eagle-import") (part "TPS22917"))
    )
    (comp (ref "U5")
      (value "TPS22917")
      (footprint "eagle-import:SOT23-6")
      (libsource (lib "eagle-import") (part "TPS22917"))
    )
    (comp (ref "U14")
      (value "TPS6216X")
      (footprint "eagle-import:8WSON")
      (libsource (lib "eagle-import") (part "TPS6216X"))
    )
    (comp (ref "C4")
      (value "0.1uF")
      (footprint "eagle-import:C0402")
      (libsource (lib "eagle-import") (part "C-EUC0402"))
    )
    (comp (ref "C5")
      (value "10uF")
      (footprint "eagle-import:C0603")
      (libsource (lib "eagle-import") (part "C-EUC0603"))
    )
    (comp (ref "C6")
      (value "22uF")
      (footprint "eagle-import:C0805")
      (libsource (lib "eagle-import") (part "C-EUC0805"))
    )
    (comp (ref "C7")
      (value "47pF")
      (footprint "eagle-import:C0402")
      (libsource (lib "eagle-import") (part "C-EUC0402"))
    )
    (comp (ref "C8")
      (value "47pF")
      (footprint "eagle-import:C0402")
      (libsource (lib "eagle-import") (part "C-EUC0402"))
    )
    (comp (ref "C9")
      (value "100nF")
      (footprint "eagle-import:C0402")
      (libsource (lib "eagle-import") (part "C-EUC0402"))
    )
    (comp (ref "C10")
      (value "47pF")
      (footprint "eagle-import:C0402")
      (libsource (lib "eagle-import") (part "C-EUC0402"))
    )
    (comp (ref "C11")
      (value "47pF")
      (footprint "eagle-import:C0402")
      (libsource (lib "eagle-import") (part "C-EUC0402"))
    )
    (comp (ref "C12")
      (value "1uF")
      (footprint "eagle-import:C0402")
      (libsource (lib "eagle-import") (part "C-EUC0402"))
    )
    (comp (ref "C13")
      (value "0.1uF")
      (footprint "eagle-import:C0402")
      (libsource (lib "eagle-import") (part "C-EUC0402"))
    )
    (comp (ref "C14")
      (value "0.1uF")
      (footprint "eagle-import:C0402")
      (libsource (lib "eagle-import") (part "C-EUC0402"))
    )
    (comp (ref "CR1")
      (value "PESD0402-140")
      (footprint "eagle-import:PESD0402")
      (fields (field (name "MANUFACTURER_PART_NUMBER") "PESD0402140"))
      (libsource (lib "eagle-import") (part "PESD0402-140"))
    )
    (comp (ref "CR2")
      (value "PESD0402-140")
      (footprint "eagle-import:PESD0402")
      (fields (field (name "MANUFACTURER_PART_NUMBER") "PESD0402140"))
      (libsource (lib "eagle-import") (part "PESD0402-140"))
    )
    (comp (ref "CR3")
      (value "PESD0402-140")
      (footprint "eagle-import:PESD0402")
      (fields (field (name "MANUFACTURER_PART_NUMBER") "PESD0402140"))
      (libsource (lib "eagle-import") (part "PESD0402-140"))
    )
    (comp (ref "CR4")
      (value "PESD0402-140")
      (footprint "eagle-import:PESD0402")
      (fields (field (name "MANUFACTURER_PART_NUMBER") "PESD0402140"))
      (libsource (lib "eagle-import") (part "PESD0402-140"))
    )
    (comp (ref "CR5")
      (value "PESD0402-140")
      (footprint "eagle-import:PESD0402")
      (fields (field (name "MANUFACTURER_PART_NUMBER") "PESD0402140"))
      (libsource (lib "eagle-import") (part "PESD0402-140"))
    )
    (comp (ref "CR6")
      (value "PESD0402-140")
      (footprint "eagle-import:PESD0402")
      (fields (field (name "MANUFACTURER_PART_NUMBER") "PESD0402140"))
      (libsource (lib "eagle-import") (part "PESD0402-140"))
    )
    (comp (ref "Q1")
      (value "BSS138")
      (footprint "eagle-import:SOT23-3")
      (libsource (lib "eagle-import") (part "BSS138"))
    )
    (comp (ref "Q2")
      (value "BSS138")
      (footprint "eagle-import:SOT23-3")
      (libsource (lib "eagle-import") (part "BSS138"))
    )
    (comp (ref "R5")
      (value "0")
      (footprint "eagle-import:R0402")
      (libsource (lib "eagle-import") (part "R-US_R0402"))
    )
    (comp (ref "R6")
      (value "0")
      (footprint "eagle-import:R0402")
      (libsource (lib "eagle-import") (part "R-US_R0402"))
    )
    (comp (ref "R10")
      (value "1M")
      (footprint "eagle-import:R0402")
      (libsource (lib "eagle-import") (part "R-US_R0402"))
    )
    (comp (ref "R11")
      (value "1M")
      (footprint "eagle-import:R0402")
      (libsource (lib "eagle-import") (part "R-US_R0402"))
    )
    (comp (ref "R18")
      (value "0")
      (footprint "eagle-import:R0402")
      (libsource (lib "eagle-import") (part "R-US_R0402"))
    )
    (comp (ref "R19")
      (value "0")
      (footprint "eagle-import:R0402")
      (libsource (lib "eagle-import") (part "R-US_R0402"))
    )
    (comp (ref "R27")
      (value "100k")
      (footprint "eagle-import:R0402")
      (libsource (lib "eagle-import") (part "R-US_R0402"))
    )
    (comp (ref "R39")
      (value "29")
      (footprint "eagle-import:R0402")
      (libsource (lib "eagle-import") (part "R-US_R0402"))
    )
    (comp (ref "R40")
      (value "29")
      (footprint "eagle-import:R0402")
      (libsource (lib "eagle-import") (part "R-US_R0402"))
    )
    (comp (ref "SJ3")
      (value "SOLDERJUMPERCLOSED")
      (footprint "eagle-import:SOLDERJUMPER_CLOSEDWIRE")
      (libsource (lib "eagle-import") (part "Charles_10020430_SOLDERJUMPERCLOSED"))
    )
    (comp (ref "SJ4")
      (value "SOLDERJUMPERCLOSED")
      (footprint "eagle-import:SOLDERJUMPER_CLOSEDWIRE")
      (libsource (lib "eagle-import") (part "Charles_10020430_SOLDERJUMPERCLOSED"))
    )
    (comp (ref "SJ5")
      (value "SOLDERJUMPERCLOSED")
      (footprint "eagle-import:SOLDERJUMPER_CLOSEDWIRE")
      (libsource (lib "eagle-import") (part "Charles_10020430_SOLDERJUMPERCLOSED"))
    )
    (comp (ref "SJ6")
      (value "SOLDERJUMPERCLOSED")
      (footprint "eagle-import:SOLDERJUMPER_CLOSEDWIRE")
      (libsource (lib "eagle-import") (part "Charles_10020430_SOLDERJUMPERCLOSED"))
    )
    (comp (ref "SJ7")
      (value "SOLDERJUMPERCLOSED")
      (footprint "eagle-import:SOLDERJUMPER_CLOSEDWIRE")
      (libsource (lib "eagle-import") (part "Charles_10020430_SOLDERJUMPERCLOSED"))
    )
    (comp (ref "U$5")
      (value "SIM_SD_MOLEX")
      (footprint "eagle-import:SIM_SD_MOLEX")
      (libsource (lib "eagle-import") (part "SIM_SD_MOLEX"))
    )
    (comp (ref "U$6")
      (value "MICRO_USB")
      (footprint "eagle-import:MOLEX_USB")
      (libsource (lib "eagle-import") (part "MICRO_USB"))
    )
    (comp (ref "U2")
      (value "SN74AVC4T774PWR")
      (footprint "eagle-import:PW16")
      (libsource (lib "eagle-import") (part "SN74AVC4T774PWR"))
    )
    (comp (ref "U6")
      (value "SARA-R404M")
      (footprint "eagle-import:SARA-R404M")
      (libsource (lib "eagle-import") (part "SARA-R404M"))
    )
    (comp (ref "X1")
      (value "ANTENNA_U.FL")
      (footprint "eagle-import:U.FL")
      (libsource (lib "eagle-import") (part "ANTENNA_U.FL"))
    )
    (comp (ref "C32")
      (value "0.1uF")
      (footprint "eagle-import:C0402")
      (libsource (lib "eagle-import") (part "C-EUC0402"))
    )
    (comp (ref "C33")
      (value "0.1uF")
      (footprint "eagle-import:C0402")
      (libsource (lib "eagle-import") (part "C-EUC0402"))
    )
    (comp (ref "C34")
      (value "0.1uF")
      (footprint "eagle-import:C0402")
      (libsource (lib "eagle-import") (part "C-EUC0402"))
    )
    (comp (ref "C36")
      (value "0.1uF")
      (footprint "eagle-import:C0402")
      (libsource (lib "eagle-import") (part "C-EUC0402"))
    )
    (comp (ref "CR7")
      (value "PESD0402-140")
      (footprint "eagle-import:PESD0402")
      (fields (field (name "MANUFACTURER_PART_NUMBER") "PESD0402140"))
      (libsource (lib "eagle-import") (part "PESD0402-140"))
    )
    (comp (ref "CR8")
      (value "PESD0402-140")
      (footprint "eagle-import:PESD0402")
      (fields (field (name "MANUFACTURER_PART_NUMBER") "PESD0402140"))
      (libsource (lib "eagle-import") (part "PESD0402-140"))
    )
    (comp (ref "J7")
      (value "MICRO_USB_VERTICAL")
      (footprint "eagle-import:MICRO_USB_VERTICAL")
      (libsource (lib "eagle-import") (part "MICRO_USB_VERTICAL"))
    )
    (comp (ref "LED1")
      (value "LEDCHIP-LED0603")
      (footprint "eagle-import:CHIP-LED0603")
      (libsource (lib "eagle-import") (part "LEDCHIP-LED0603"))
    )
    (comp (ref "LED2")
      (value "LEDCHIP-LED0603")
      (footprint "eagle-import:CHIP-LED0603")
      (libsource (lib "eagle-import") (part "LEDCHIP-LED0603"))
    )
    (comp (ref "LED3")
      (value "LEDCHIP-LED0603")
      (footprint "eagle-import:CHIP-LED0603")
      (libsource (lib "eagle-import") (part "LEDCHIP-LED0603"))
    )
    (comp (ref "LED4")
      (value "LEDCHIP-LED0603")
      (footprint "eagle-import:CHIP-LED0603")
      (libsource (lib "eagle-import") (part "LEDCHIP-LED0603"))
    )
    (comp (ref "R1")
      (value "100k")
      (footprint "eagle-import:R0402")
      (libsource (lib "eagle-import") (part "R-US_R0402"))
    )
    (comp (ref "R2")
      (value "100k")
      (footprint "eagle-import:R0402")
      (libsource (lib "eagle-import") (part "R-US_R0402"))
    )
    (comp (ref "R32")
      (value "4.7k")
      (footprint "eagle-import:R0402")
      (libsource (lib "eagle-import") (part "R-US_R0402"))
    )
    (comp (ref "R33")
      (value "4.7k")
      (footprint "eagle-import:R0402")
      (libsource (lib "eagle-import") (part "R-US_R0402"))
    )
    (comp (ref "R34")
      (value "100k")
      (footprint "eagle-import:R0402")
      (libsource (lib "eagle-import") (part "R-US_R0402"))
    )
    (comp (ref "R35")
      (value "100k")
      (footprint "eagle-import:R0402")
      (libsource (lib "eagle-import") (part "R-US_R0402"))
    )
    (comp (ref "R36")
      (value "100k")
      (footprint "eagle-import:R0402")
      (libsource (lib "eagle-import") (part "R-US_R0402"))
    )
    (comp (ref "S1")
      (value "KMR731NG")
      (footprint "eagle-import:KMR731NG")
      (libsource (lib "eagle-import") (part "KMR731NG"))
    )
    (comp (ref "S2")
      (value "KMR731NG")
      (footprint "eagle-import:KMR731NG")
      (libsource (lib "eagle-import") (part "KMR731NG"))
    )
    (comp (ref "S3")
      (value "KMR731NG")
      (footprint "eagle-import:KMR731NG")
      (libsource (lib "eagle-import") (part "KMR731NG"))
    )
    (comp (ref "S4")
      (value "KMR731NG")
      (footprint "eagle-import:KMR731NG")
      (libsource (lib "eagle-import") (part "KMR731NG"))
    )
    (comp (ref "S5")
      (value "KMR731NG")
      (footprint "eagle-import:KMR731NG")
      (libsource (lib "eagle-import") (part "KMR731NG"))
    )
    (comp (ref "SJ16")
      (value "SOLDERJUMPERREFLOW_NOPASTE")
      (footprint "eagle-import:SOLDERJUMPER_REFLOW_NOPASTE")
      (libsource (lib "eagle-import") (part "Charles_10020430_SOLDERJUMPERREFLOW_NOPASTE"))
    )
    (comp (ref "SJ17")
      (value "SOLDERJUMPERREFLOW_NOPASTE")
      (footprint "eagle-import:SOLDERJUMPER_REFLOW_NOPASTE")
      (libsource (lib "eagle-import") (part "Charles_10020430_SOLDERJUMPERREFLOW_NOPASTE"))
    )
    (comp (ref "SJ18")
      (value "SOLDERJUMPERREFLOW_NOPASTE")
      (footprint "eagle-import:SOLDERJUMPER_REFLOW_NOPASTE")
      (libsource (lib "eagle-import") (part "Charles_10020430_SOLDERJUMPERREFLOW_NOPASTE"))
    )
    (comp (ref "U$1")
      (value "STM32L422RBT6")
      (footprint "eagle-import:QFP50P1200X1200X160-64")
      (libsource (lib "eagle-import") (part "STM32L422RBT6"))
    )
  )
  (nets
    (net (code "1") (name "+3V3_GPS") (class "Default")
      (node (ref "J3") (pin "1") (pinfunction "1_1") (pintype "passive"))
      (node (ref "R42") (pin "2") (pinfunction "2_2") (pintype "passive"))
      (node (ref "U$8") (pin "P$7") (pinfunction "VCC_IO_P$7") (pintype "bidirectional"))
      (node (ref "U$8") (pin "P$8") (pinfunction "VCC_P$8") (pintype "bidirectional"))
    )
    (net (code "2") (name "+3V3_LORA") (class "Default")
      (node (ref "C46") (pin "2") (pinfunction "2_2") (pintype "passive"))
      (node (ref "C47") (pin "2") (pinfunction "2_2") (pintype "passive"))
      (node (ref "J2") (pin "1") (pinfunction "1_1") (pintype "passive"))
      (node (ref "R41") (pin "2") (pinfunction "2_2") (pintype "passive"))
      (node (ref "U$7") (pin "1") (pinfunction "VDD_IN_1") (pintype "bidirectional"))
      (node (ref "U$7") (pin "10") (pinfunction "VBAT_10") (pintype "bidirectional"))
      (node (ref "U$7") (pin "11") (pinfunction "VBAT_IO_11") (pintype "bidirectional"))
      (node (ref "U$9") (pin "P$6") (pinfunction "VDD_P$6") (pintype "bidirectional"))
    )
    (net (code "3") (name "+3V3_MAIN") (class "Default")
      (node (ref "C13") (pin "1") (pinfunction "1_1") (pintype "passive"))
      (node (ref "C20") (pin "1") (pinfunction "1_1") (pintype "passive"))
      (node (ref "C25") (pin "1") (pinfunction "1_1") (pintype "passive"))
      (node (ref "C28") (pin "1") (pinfunction "1_1") (pintype "passive"))
      (node (ref "C31") (pin "1") (pinfunction "1_1") (pintype "passive"))
      (node (ref "C32") (pin "1") (pinfunction "1_1") (pintype "passive"))
      (node (ref "C33") (pin "1") (pinfunction "1_1") (pintype "passive"))
      (node (ref "C34") (pin "1") (pinfunction "1_1") (pintype "passive"))
      (node (ref "C36") (pin "1") (pinfunction "1_1") (pintype "passive"))
      (node (ref "J1") (pin "1") (pinfunction "1_1") (pintype "bidirectional"))
      (node (ref "R18") (pin "1") (pinfunction "1_1") (pintype "passive"))
      (node (ref "R28") (pin "2") (pinfunction "2_2") (pintype "passive"))
      (node (ref "R30") (pin "2") (pinfunction "2_2") (pintype "passive"))
      (node (ref "R31") (pin "2") (pinfunction "2_2") (pintype "passive"))
      (node (ref "R32") (pin "1") (pinfunction "1_1") (pintype "passive"))
      (node (ref "R33") (pin "1") (pinfunction "1_1") (pintype "passive"))
      (node (ref "R37") (pin "2") (pinfunction "2_2") (pintype "passive"))
      (node (ref "R5") (pin "2") (pinfunction "2_2") (pintype "passive"))
      (node (ref "R9") (pin "2") (pinfunction "2_2") (pintype "passive"))
      (node (ref "SJ16") (pin "1") (pinfunction "1_1") (pintype "passive"))
      (node (ref "SJ18") (pin "1") (pinfunction "1_1") (pintype "passive"))
      (node (ref "U$1") (pin "19") (pinfunction "VDD1_19") (pintype "bidirectional"))
      (node (ref "U$1") (pin "32") (pinfunction "VDD2_32") (pintype "bidirectional"))
      (node (ref "U$1") (pin "48") (pinfunction "VDDUSB_48") (pintype "bidirectional"))
      (node (ref "U$1") (pin "64") (pinfunction "VDD3_64") (pintype "bidirectional"))
      (node (ref "U$4") (pin "1") (pinfunction "1_1") (pintype "passive"))
      (node (ref "U14") (pin "P$6") (pinfunction "VOS_P$6") (pintype "bidirectional"))
      (node (ref "U2") (pin "16") (pinfunction "VCCA_16") (pintype "power_in"))
      (node (ref "U3") (pin "1") (pinfunction "VIN_1") (pintype "bidirectional"))
      (node (ref "U4") (pin "1") (pinfunction "VIN_1") (pintype "bidirectional"))
      (node (ref "U5") (pin "1") (pinfunction "VIN_1") (pintype "bidirectional"))
    )
    (net (code "4") (name "+3V3_SD") (class "Default")
      (node (ref "J4") (pin "1") (pinfunction "1_1") (pintype "passive"))
      (node (ref "R27") (pin "2") (pinfunction "2_2") (pintype "passive"))
      (node (ref "R43") (pin "2") (pinfunction "2_2") (pintype "passive"))
      (node (ref "U$5") (pin "T4") (pinfunction "VDD_T4") (pintype "bidirectional"))
    )
    (net (code "5") (name "+3V7_CELL") (class "Default")
      (node (ref "C12") (pin "1") (pinfunction "1_1") (pintype "passive"))
      (node (ref "C4") (pin "1") (pinfunction "1_1") (pintype "passive"))
      (node (ref "C5") (pin "1") (pinfunction "1_1") (pintype "passive"))
      (node (ref "C6") (pin "1") (pinfunction "1_1") (pintype "passive"))
      (node (ref "J6") (pin "1") (pinfunction "1_1") (pintype "passive"))
      (node (ref "R14") (pin "2") (pinfunction "2_2") (pintype "passive"))
      (node (ref "R16") (pin "2") (pinfunction "2_2") (pintype "passive"))
      (node (ref "R20") (pin "2") (pinfunction "2_2") (pintype "passive"))
      (node (ref "R22") (pin "2") (pinfunction "2_2") (pintype "passive"))
      (node (ref "R24") (pin "2") (pinfunction "2_2") (pintype "passive"))
      (node (ref "R26") (pin "2") (pinfunction "2_2") (pintype "passive"))
      (node (ref "R38") (pin "2") (pinfunction "2_2") (pintype "passive"))
      (node (ref "U6") (pin "51") (pinfunction "VCC_51") (pintype "bidirectional"))
      (node (ref "U6") (pin "52") (pinfunction "VCC_52") (pintype "bidirectional"))
      (node (ref "U6") (pin "53") (pinfunction "VCC_53") (pintype "bidirectional"))
    )
    (net (code "6") (name "CELL_CTS") (class "Default")
      (node (ref "JP2") (pin "2") (pinfunction "2_2") (pintype "passive"))
      (node (ref "U$1") (pin "14") (pinfunction "PA0_14") (pintype "bidirectional"))
      (node (ref "U2") (pin "4") (pinfunction "A2_4") (pintype "bidirectional"))
    )
    (net (code "7") (name "CELL_POWER_EN") (class "Default")
      (node (ref "SJ10") (pin "1") (pinfunction "1_1") (pintype "passive"))
      (node (ref "U$1") (pin "25") (pinfunction "PC5_25") (pintype "bidirectional"))
    )
    (net (code "8") (name "CELL_RTS") (class "Default")
      (node (ref "JP2") (pin "3") (pinfunction "3_3") (pintype "passive"))
      (node (ref "U$1") (pin "15") (pinfunction "PA1_15") (pintype "bidirectional"))
      (node (ref "U2") (pin "3") (pinfunction "A1_3") (pintype "bidirectional"))
    )
    (net (code "9") (name "CELL_RX") (class "Default")
      (node (ref "JP2") (pin "4") (pinfunction "4_4") (pintype "passive"))
      (node (ref "U$1") (pin "17") (pinfunction "PA3_17") (pintype "bidirectional"))
      (node (ref "U2") (pin "6") (pinfunction "A4_6") (pintype "bidirectional"))
    )
    (net (code "10") (name "CELL_TURN_ON") (class "Default")
      (node (ref "Q2") (pin "1") (pinfunction "G_1") (pintype "bidirectional"))
      (node (ref "R11") (pin "2") (pinfunction "2_2") (pintype "passive"))
      (node (ref "U$1") (pin "20") (pinfunction "PA4_20") (pintype "bidirectional"))
    )
    (net (code "11") (name "CELL_TX") (class "Default")
      (node (ref "JP2") (pin "5") (pinfunction "5_5") (pintype "passive"))
      (node (ref "U$1") (pin "16") (pinfunction "PA2_16") (pintype "bidirectional"))
      (node (ref "U2") (pin "5") (pinfunction "A3_5") (pintype "bidirectional"))
    )
    (net (code "12") (name "DIO2") (class "Default")
      (node (ref "R4") (pin "1") (pinfunction "1_1") (pintype "passive"))
      (node (ref "U$7") (pin "12") (pinfunction "DIO2_12") (pintype "bidirectional"))
    )
    (net (code "13") (name "GND") (class "Default")
      (node (ref "C1") (pin "2") (pinfunction "2_2") (pintype "passive"))
      (node (ref "C10") (pin "2") (pinfunction "2_2") (pintype "passive"))
      (node (ref "C11") (pin "2") (pinfunction "2_2") (pintype "passive"))
      (node (ref "C12") (pin "2") (pinfunction "2_2") (pintype "passive"))
      (node (ref "C13") (pin "2") (pinfunction "2_2") (pintype "passive"))
      (node (ref "C14") (pin "2") (pinfunction "2_2") (pintype "passive"))
      (node (ref "C15") (pin "2") (pinfunction "2_2") (pintype "passive"))
      (node (ref "C16") (pin "2") (pinfunction "2_2") (pintype "passive"))
      (node (ref "C17") (pin "2") (pinfunction "2_2") (pintype "passive"))
      (node (ref "C18") (pin "2") (pinfunction "2_2") (pintype "passive"))
      (node (ref "C19") (pin "2") (pinfunction "2_2") (pintype "passive"))
      (node (ref "C2") (pin "2") (pinfunction "2_2") (pintype "passive"))
      (node (ref "C20") (pin "2") (pinfunction "2_2") (pintype "passive"))
      (node (ref "C21") (pin "2") (pinfunction "2_2") (pintype "passive"))
      (node (ref "C22") (pin "2") (pinfunction "2_2") (pintype "passive"))
      (node (ref "C23") (pin "2") (pinfunction "2_2") (pintype "passive"))
      (node (ref "C24") (pin "2") (pinfunction "2_2") (pintype "passive"))
      (node (ref "C25") (pin "2") (pinfunction "2_2") (pintype "passive"))
      (node (ref "C26") (pin "2") (pinfunction "2_2") (pintype "passive"))
      (node (ref "C27") (pin "2") (pinfunction "2_2") (pintype "passive"))
      (node (ref "C28") (pin "2") (pinfunction "2_2") (pintype "passive"))
      (node (ref "C29") (pin "2") (pinfunction "2_2") (pintype "passive"))
      (node (ref "C30") (pin "2") (pinfunction "2_2") (pintype "passive"))
      (node (ref "C31") (pin "2") (pinfunction "2_2") (pintype "passive"))
      (node (ref "C32") (pin "2") (pinfunction "2_2") (pintype "passive"))
      (node (ref "C33") (pin "2") (pinfunction "2_2") (pintype "passive"))
      (node (ref "C34") (pin "2") (pinfunction "2_2") (pintype "passive"))
      (node (ref "C36") (pin "2") (pinfunction "2_2") (pintype "passive"))
      (node (ref "C37") (pin "2") (pinfunction "2_2") (pintype "passive"))
      (node (ref "C39") (pin "2") (pinfunction "2_2") (pintype "passive"))
      (node (ref "C4") (pin "2") (pinfunction "2_2") (pintype "passive"))
      (node (ref "C41") (pin "2") (pinfunction "2_2") (pintype "passive"))
      (node (ref "C42") (pin "2") (pinfunction "2_2") (pintype "passive"))
      (node (ref "C44") (pin "2") (pinfunction "2_2") (pintype "passive"))
      (node (ref "C45") (pin "2") (pinfunction "2_2") (pintype "passive"))
      (node (ref "C46") (pin "1") (pinfunction "1_1") (pintype "passive"))
      (node (ref "C47") (pin "1") (pinfunction "1_1") (pintype "passive"))
      (node (ref "C48") (pin "1") (pinfunction "1_1") (pintype "passive"))
      (node (ref "C5") (pin "2") (pinfunction "2_2") (pintype "passive"))
      (node (ref "C6") (pin "2") (pinfunction "2_2") (pintype "passive"))
      (node (ref "C7") (pin "2") (pinfunction "2_2") (pintype "passive"))
      (node (ref "C8") (pin "2") (pinfunction "2_2") (pintype "passive"))
      (node (ref "C9") (pin "2") (pinfunction "2_2") (pintype "passive"))
      (node (ref "CR1") (pin "1") (pinfunction "11_1") (pintype "passive"))
      (node (ref "CR2") (pin "1") (pinfunction "11_1") (pintype "passive"))
      (node (ref "CR3") (pin "1") (pinfunction "11_1") (pintype "passive"))
      (node (ref "CR4") (pin "1") (pinfunction "11_1") (pintype "passive"))
      (node (ref "CR5") (pin "1") (pinfunction "11_1") (pintype "passive"))
      (node (ref "CR6") (pin "1") (pinfunction "11_1") (pintype "passive"))
      (node (ref "CR7") (pin "1") (pinfunction "11_1") (pintype "passive"))
      (node (ref "CR8") (pin "1") (pinfunction "11_1") (pintype "passive"))
      (node (ref "J1") (pin "6") (pinfunction "6_6") (pintype "bidirectional"))
      (node (ref "J5") (pin "1") (pinfunction "-_1") (pintype "bidirectional"))
      (node (ref "J7") (pin "5") (pinfunction "GND_5") (pintype "bidirectional"))
      (node (ref "JP1") (pin "6") (pinfunction "6_6") (pintype "passive"))
      (node (ref "JP2") (pin "6") (pinfunction "6_6") (pintype "passive"))
      (node (ref "JP4") (pin "6") (pinfunction "6_6") (pintype "passive"))
      (node (ref "LED10") (pin "C") (pinfunction "C_C") (pintype "passive"))
      (node (ref "LED11") (pin "C") (pinfunction "C_C") (pintype "passive"))
      (node (ref "LED13") (pin "C") (pinfunction "C_C") (pintype "passive"))
      (node (ref "LED14") (pin "C") (pinfunction "C_C") (pintype "passive"))
      (node (ref "LED15") (pin "C") (pinfunction "C_C") (pintype "passive"))
      (node (ref "Q1") (pin "3") (pinfunction "D_3") (pintype "bidirectional"))
      (node (ref "Q2") (pin "3") (pinfunction "D_3") (pintype "bidirectional"))
      (node (ref "R1") (pin "2") (pinfunction "2_2") (pintype "passive"))
      (node (ref "R10") (pin "1") (pinfunction "1_1") (pintype "passive"))
      (node (ref "R11") (pin "1") (pinfunction "1_1") (pintype "passive"))
      (node (ref "R13") (pin "1") (pinfunction "1_1") (pintype "passive"))
      (node (ref "R15") (pin "1") (pinfunction "1_1") (pintype "passive"))
      (node (ref "R17") (pin "1") (pinfunction "1_1") (pintype "passive"))
      (node (ref "R19") (pin "1") (pinfunction "1_1") (pintype "passive"))
      (node (ref "R2") (pin "2") (pinfunction "2_2") (pintype "passive"))
      (node (ref "R21") (pin "1") (pinfunction "1_1") (pintype "passive"))
      (node (ref "R23") (pin "1") (pinfunction "1_1") (pintype "passive"))
      (node (ref "R25") (pin "1") (pinfunction "1_1") (pintype "passive"))
      (node (ref "R34") (pin "2") (pinfunction "2_2") (pintype "passive"))
      (node (ref "R35") (pin "2") (pinfunction "2_2") (pintype "passive"))
      (node (ref "R36") (pin "2") (pinfunction "2_2") (pintype "passive"))
      (node (ref "R6") (pin "2") (pinfunction "2_2") (pintype "passive"))
      (node (ref "S1") (pin "P$1") (pinfunction "P$1_P$1") (pintype "bidirectional"))
      (node (ref "S2") (pin "P$1") (pinfunction "P$1_P$1") (pintype "bidirectional"))
      (node (ref "S3") (pin "P$1") (pinfunction "P$1_P$1") (pintype "bidirectional"))
      (node (ref "S4") (pin "P$1") (pinfunction "P$1_P$1") (pintype "bidirectional"))
      (node (ref "S5") (pin "P$1") (pinfunction "P$1_P$1") (pintype "bidirectional"))
      (node (ref "SJ17") (pin "1") (pinfunction "1_1") (pintype "passive"))
      (node (ref "SJ3") (pin "1") (pinfunction "1_1") (pintype "passive"))
      (node (ref "U$1") (pin "18") (pinfunction "VSS1_18") (pintype "bidirectional"))
      (node (ref "U$1") (pin "31") (pinfunction "VSS2_31") (pintype "bidirectional"))
      (node (ref "U$1") (pin "47") (pinfunction "VSS3_47") (pintype "bidirectional"))
      (node (ref "U$1") (pin "63") (pinfunction "VSS4_63") (pintype "bidirectional"))
      (node (ref "U$11") (pin "2") (pinfunction "GND2_2") (pintype "bidirectional"))
      (node (ref "U$11") (pin "4") (pinfunction "GND1_4") (pintype "bidirectional"))
      (node (ref "U$11") (pin "5") (pinfunction "GND2_5") (pintype "bidirectional"))
      (node (ref "U$2") (pin "P$2") (pinfunction "GND_P$2") (pintype "bidirectional"))
      (node (ref "U$2") (pin "P$3") (pinfunction "GND_P$3") (pintype "bidirectional"))
      (node (ref "U$2") (pin "P$5") (pinfunction "GND_P$5") (pintype "bidirectional"))
      (node (ref "U$5") (pin "C5") (pinfunction "GND_C5") (pintype "bidirectional"))
      (node (ref "U$5") (pin "G1") (pinfunction "GND_G1") (pintype "bidirectional"))
      (node (ref "U$5") (pin "G2") (pinfunction "GND_G2") (pintype "bidirectional"))
      (node (ref "U$5") (pin "G3") (pinfunction "GND_G3") (pintype "bidirectional"))
      (node (ref "U$5") (pin "G4") (pinfunction "GND_G4") (pintype "bidirectional"))
      (node (ref "U$5") (pin "G5") (pinfunction "GND_G5") (pintype "bidirectional"))
      (node (ref "U$5") (pin "G6") (pinfunction "GND_G6") (pintype "bidirectional"))
      (node (ref "U$5") (pin "G7") (pinfunction "GND_G7") (pintype "bidirectional"))
      (node (ref "U$5") (pin "G8") (pinfunction "GND_G8") (pintype "bidirectional"))
      (node (ref "U$5") (pin "T6") (pinfunction "GND_T6") (pintype "bidirectional"))
      (node (ref "U$6") (pin "P$5") (pinfunction "GND_P$5") (pintype "bidirectional"))
      (node (ref "U$7") (pin "2") (pinfunction "GND1_2") (pintype "bidirectional"))
      (node (ref "U$7") (pin "20") (pinfunction "GND4_20") (pintype "bidirectional"))
      (node (ref "U$7") (pin "25") (pinfunction "GND1_25") (pintype "bidirectional"))
      (node (ref "U$7") (pin "5") (pinfunction "GND2_5") (pintype "bidirectional"))
      (node (ref "U$7") (pin "8") (pinfunction "GND3_8") (pintype "bidirectional"))
      (node (ref "U$8") (pin "P$1") (pinfunction "GND_P$1") (pintype "bidirectional"))
      (node (ref "U$8") (pin "P$10") (pinfunction "GND_P$10") (pintype "bidirectional"))
      (node (ref "U$8") (pin "P$12") (pinfunction "GND_P$12") (pintype "bidirectional"))
      (node (ref "U$9") (pin "P$2") (pinfunction "GND_P$2") (pintype "bidirectional"))
      (node (ref "U1") (pin "2") (pinfunction "GND_2") (pintype "bidirectional"))
      (node (ref "U10") (pin "2") (pinfunction "S_2") (pintype "bidirectional"))
      (node (ref "U11") (pin "2") (pinfunction "S_2") (pintype "bidirectional"))
      (node (ref "U12") (pin "2") (pinfunction "S_2") (pintype "bidirectional"))
      (node (ref "U14") (pin "P$1") (pinfunction "PGND_P$1") (pintype "bidirectional"))
      (node (ref "U14") (pin "P$4") (pinfunction "AGND_P$4") (pintype "bidirectional"))
      (node (ref "U14") (pin "P$5") (pinfunction "FB_P$5") (pintype "bidirectional"))
      (node (ref "U14") (pin "P$9") (pinfunction "AGND_P$9") (pintype "bidirectional"))
      (node (ref "U2") (pin "10") (pinfunction "GND_10") (pintype "power_in"))
      (node (ref "U2") (pin "9") (pinfunction "~{OE}_9") (pintype "input"))
      (node (ref "U3") (pin "2") (pinfunction "GND_2") (pintype "bidirectional"))
      (node (ref "U4") (pin "2") (pinfunction "GND_2") (pintype "bidirectional"))
      (node (ref "U5") (pin "2") (pinfunction "GND_2") (pintype "bidirectional"))
      (node (ref "U6") (pin "1") (pinfunction "GND_1") (pintype "bidirectional"))
      (node (ref "U6") (pin "14") (pinfunction "GND_14") (pintype "bidirectional"))
      (node (ref "U6") (pin "20") (pinfunction "GND_20") (pintype "bidirectional"))
      (node (ref "U6") (pin "21") (pinfunction "GND_21") (pintype "bidirectional"))
      (node (ref "U6") (pin "22") (pinfunction "GND_22") (pintype "bidirectional"))
      (node (ref "U6") (pin "3") (pinfunction "GND_3") (pintype "bidirectional"))
      (node (ref "U6") (pin "30") (pinfunction "GND_30") (pintype "bidirectional"))
      (node (ref "U6") (pin "32") (pinfunction "GND_32") (pintype "bidirectional"))
      (node (ref "U6") (pin "43") (pinfunction "GND_43") (pintype "bidirectional"))
      (node (ref "U6") (pin "5") (pinfunction "GND_5") (pintype "bidirectional"))
      (node (ref "U6") (pin "50") (pinfunction "GND_50") (pintype "bidirectional"))
      (node (ref "U6") (pin "54") (pinfunction "GND_54") (pintype "bidirectional"))
      (node (ref "U6") (pin "55") (pinfunction "GND_55") (pintype "bidirectional"))
      (node (ref "U6") (pin "57") (pinfunction "GND_57") (pintype "bidirectional"))
      (node (ref "U6") (pin "58") (pinfunction "GND_58") (pintype "bidirectional"))
      (node (ref "U6") (pin "59") (pinfunction "GND_59") (pintype "bidirectional"))
      (node (ref "U6") (pin "60") (pinfunction "GND_60") (pintype "bidirectional"))
      (node (ref "U6") (pin "61") (pinfunction "GND_61") (pintype "bidirectional"))
      (node (ref "U6") (pin "63") (pinfunction "GND_63") (pintype "bidirectional"))
      (node (ref "U6") (pin "64") (pinfunction "GND_64") (pintype "bidirectional"))
      (node (ref "U6") (pin "65") (pinfunction "GND_65") (pintype "bidirectional"))
      (node (ref "U6") (pin "66") (pinfunction "GND_66") (pintype "bidirectional"))
      (node (ref "U6") (pin "67") (pinfunction "GND_67") (pintype "bidirectional"))
      (node (ref "U6") (pin "68") (pinfunction "GND_68") (pintype "bidirectional"))
      (node (ref "U6") (pin "69") (pinfunction "GND_69") (pintype "bidirectional"))
      (node (ref "U6") (pin "70") (pinfunction "GND_70") (pintype "bidirectional"))
      (node (ref "U6") (pin "71") (pinfunction "GND_71") (pintype "bidirectional"))
      (node (ref "U6") (pin "72") (pinfunction "GND_72") (pintype "bidirectional"))
      (node (ref "U6") (pin "73") (pinfunction "GND_73") (pintype "bidirectional"))
      (node (ref "U6") (pin "74") (pinfunction "GND_74") (pintype "bidirectional"))
      (node (ref "U6") (pin "75") (pinfunction "GND_75") (pintype "bidirectional"))
      (node (ref "U6") (pin "76") (pinfunction "GND_76") (pintype "bidirectional"))
      (node (ref "U6") (pin "77") (pinfunction "GND_77") (pintype "bidirectional"))
      (node (ref "U6") (pin "78") (pinfunction "GND_78") (pintype "bidirectional"))
      (node (ref "U6") (pin "79") (pinfunction "GND_79") (pintype "bidirectional"))
      (node (ref "U6") (pin "80") (pinfunction "GND_80") (pintype "bidirectional"))
      (node (ref "U6") (pin "81") (pinfunction "GND_81") (pintype "bidirectional"))
      (node (ref "U6") (pin "82") (pinfunction "GND_82") (pintype "bidirectional"))
      (node (ref "U6") (pin "83") (pinfunction "GND_83") (pintype "bidirectional"))
      (node (ref "U6") (pin "84") (pinfunction "GND_84") (pintype "bidirectional"))
      (node (ref "U6") (pin "85") (pinfunction "GND_85") (pintype "bidirectional"))
      (node (ref "U6") (pin "86") (pinfunction "GND_86") (pintype "bidirectional"))
      (node (ref "U6") (pin "87") (pinfunction "GND_87") (pintype "bidirectional"))
      (node (ref "U6") (pin "88") (pinfunction "GND_88") (pintype "bidirectional"))
      (node (ref "U6") (pin "89") (pinfunction "GND_89") (pintype "bidirectional"))
      (node (ref "U6") (pin "90") (pinfunction "GND_90") (pintype "bidirectional"))
      (node (ref "U6") (pin "91") (pinfunction "GND_91") (pintype "bidirectional"))
      (node (ref "U6") (pin "92") (pinfunction "GND_92") (pintype "bidirectional"))
      (node (ref "U6") (pin "93") (pinfunction "GND_93") (pintype "bidirectional"))
      (node (ref "U6") (pin "94") (pinfunction "GND_94") (pintype "bidirectional"))
      (node (ref "U6") (pin "95") (pinfunction "GND_95") (pintype "bidirectional"))
      (node (ref "U6") (pin "96") (pinfunction "GND_96") (pintype "bidirectional"))
      (node (ref "U7") (pin "2") (pinfunction "S_2") (pintype "bidirectional"))
      (node (ref "U8") (pin "2") (pinfunction "S_2") (pintype "bidirectional"))
      (node (ref "U9") (pin "2") (pinfunction "S_2") (pintype "bidirectional"))
      (node (ref "X1") (pin "1") (pinfunction "GND_1") (pintype "passive"))
      (node (ref "X1") (pin "2") (pinfunction "GND_2") (pintype "passive"))
      (node (ref "X2") (pin "GND@1") (pinfunction "GND4_GND@1") (pintype "power_in"))
      (node (ref "X2") (pin "GND@2") (pinfunction "GND3_GND@2") (pintype "power_in"))
      (node (ref "X2") (pin "GND@3") (pinfunction "GND2_GND@3") (pintype "power_in"))
      (node (ref "X2") (pin "GND@4") (pinfunction "GND1_GND@4") (pintype "power_in"))
      (node (ref "X3") (pin "GND@1") (pinfunction "GND1_GND@1") (pintype "power_in"))
      (node (ref "X3") (pin "GND@2") (pinfunction "GND2_GND@2") (pintype "power_in"))
      (node (ref "X3") (pin "GND@3") (pinfunction "GND3_GND@3") (pintype "power_in"))
      (node (ref "X3") (pin "GND@4") (pinfunction "GND4_GND@4") (pintype "power_in"))
    )
    (net (code "14") (name "GPIO1") (class "Default")
      (node (ref "R21") (pin "2") (pinfunction "2_2") (pintype "passive"))
      (node (ref "U10") (pin "1") (pinfunction "G_1") (pintype "bidirectional"))
      (node (ref "U6") (pin "16") (pinfunction "GPIO1_16") (pintype "bidirectional"))
    )
    (net (code "15") (name "GPIO2") (class "Default")
      (node (ref "R17") (pin "2") (pinfunction "2_2") (pintype "passive"))
      (node (ref "U6") (pin "23") (pinfunction "GPIO2_23") (pintype "bidirectional"))
      (node (ref "U9") (pin "1") (pinfunction "G_1") (pintype "bidirectional"))
    )
    (net (code "16") (name "GPIO3") (class "Default")
      (node (ref "R15") (pin "2") (pinfunction "2_2") (pintype "passive"))
      (node (ref "U6") (pin "24") (pinfunction "GPIO3_24") (pintype "bidirectional"))
      (node (ref "U8") (pin "1") (pinfunction "G_1") (pintype "bidirectional"))
    )
    (net (code "17") (name "GPIO4") (class "Default")
      (node (ref "R13") (pin "2") (pinfunction "2_2") (pintype "passive"))
      (node (ref "U6") (pin "25") (pinfunction "GPIO4_25") (pintype "bidirectional"))
      (node (ref "U7") (pin "1") (pinfunction "G_1") (pintype "bidirectional"))
    )
    (net (code "18") (name "GPIO5") (class "Default")
      (node (ref "R25") (pin "2") (pinfunction "2_2") (pintype "passive"))
      (node (ref "U12") (pin "1") (pinfunction "G_1") (pintype "bidirectional"))
      (node (ref "U6") (pin "42") (pinfunction "GPIO5_42") (pintype "bidirectional"))
    )
    (net (code "19") (name "GPIO6") (class "Default")
      (node (ref "R23") (pin "2") (pinfunction "2_2") (pintype "passive"))
      (node (ref "U11") (pin "1") (pinfunction "G_1") (pintype "bidirectional"))
      (node (ref "U6") (pin "19") (pinfunction "GPIO6_19") (pintype "bidirectional"))
    )
    (net (code "20") (name "GPS_POWER_EN") (class "Default")
      (node (ref "SJ12") (pin "1") (pinfunction "1_1") (pintype "passive"))
      (node (ref "U$1") (pin "26") (pinfunction "PB0_26") (pintype "bidirectional"))
    )
    (net (code "21") (name "GPS_RX") (class "Default")
      (node (ref "JP4") (pin "4") (pinfunction "4_4") (pintype "passive"))
      (node (ref "SJ2") (pin "1") (pinfunction "1_1") (pintype "passive"))
      (node (ref "U$1") (pin "42") (pinfunction "PA9_42") (pintype "bidirectional"))
    )
    (net (code "22") (name "GPS_SCL") (class "Default")
      (node (ref "JP4") (pin "2") (pinfunction "2_2") (pintype "passive"))
      (node (ref "R32") (pin "2") (pinfunction "2_2") (pintype "passive"))
      (node (ref "SJ8") (pin "2") (pinfunction "2_2") (pintype "passive"))
      (node (ref "U$1") (pin "8") (pinfunction "PC0_8") (pintype "bidirectional"))
    )
    (net (code "23") (name "GPS_SDA") (class "Default")
      (node (ref "JP4") (pin "3") (pinfunction "3_3") (pintype "passive"))
      (node (ref "R33") (pin "2") (pinfunction "2_2") (pintype "passive"))
      (node (ref "SJ9") (pin "2") (pinfunction "2_2") (pintype "passive"))
      (node (ref "U$1") (pin "9") (pinfunction "PC1_9") (pintype "bidirectional"))
    )
    (net (code "24") (name "GPS_TX") (class "Default")
      (node (ref "JP4") (pin "5") (pinfunction "5_5") (pintype "passive"))
      (node (ref "SJ1") (pin "1") (pinfunction "1_1") (pintype "passive"))
      (node (ref "U$1") (pin "43") (pinfunction "PA10_43") (pintype "bidirectional"))
    )
    (net (code "25") (name "JTAG_RESET") (class "Default")
      (node (ref "J1") (pin "5") (pinfunction "5_5") (pintype "bidirectional"))
      (node (ref "S1") (pin "P$4") (pinfunction "P$4_P$4") (pintype "bidirectional"))
      (node (ref "U$1") (pin "7") (pinfunction "NRST_7") (pintype "bidirectional"))
    )
    (net (code "26") (name "JTAG_SWCLK") (class "Default")
      (node (ref "J1") (pin "3") (pinfunction "3_3") (pintype "bidirectional"))
      (node (ref "U$1") (pin "49") (pinfunction "PA14_49") (pintype "bidirectional"))
    )
    (net (code "27") (name "JTAG_SWDIO") (class "Default")
      (node (ref "J1") (pin "2") (pinfunction "2_2") (pintype "bidirectional"))
      (node (ref "U$1") (pin "46") (pinfunction "PA13_46") (pintype "bidirectional"))
    )
    (net (code "28") (name "JTAG_SWO") (class "Default")
      (node (ref "J1") (pin "4") (pinfunction "4_4") (pintype "bidirectional"))
    )
    (net (code "29") (name "LORA_MISO") (class "Default")
      (node (ref "JP1") (pin "3") (pinfunction "3_3") (pintype "passive"))
      (node (ref "U$1") (pin "56") (pinfunction "PB4_56") (pintype "bidirectional"))
      (node (ref "U$7") (pin "16") (pinfunction "MISO_16") (pintype "bidirectional"))
    )
    (net (code "30") (name "LORA_MOSI") (class "Default")
      (node (ref "JP1") (pin "2") (pinfunction "2_2") (pintype "passive"))
      (node (ref "U$1") (pin "57") (pinfunction "PB5_57") (pintype "bidirectional"))
      (node (ref "U$7") (pin "17") (pinfunction "MOSI_17") (pintype "bidirectional"))
    )
    (net (code "31") (name "LORA_NSS") (class "Default")
      (node (ref "JP1") (pin "5") (pinfunction "5_5") (pintype "passive"))
      (node (ref "U$1") (pin "50") (pinfunction "PA15_50") (pintype "bidirectional"))
      (node (ref "U$7") (pin "19") (pinfunction "NSS_19") (pintype "bidirectional"))
    )
    (net (code "32") (name "LORA_POWER_EN") (class "Default")
      (node (ref "SJ11") (pin "1") (pinfunction "1_1") (pintype "passive"))
      (node (ref "U$1") (pin "23") (pinfunction "PA7_23") (pintype "bidirectional"))
    )
    (net (code "33") (name "LORA_SCK") (class "Default")
      (node (ref "JP1") (pin "4") (pinfunction "4_4") (pintype "passive"))
      (node (ref "U$1") (pin "55") (pinfunction "PB3_55") (pintype "bidirectional"))
      (node (ref "U$7") (pin "18") (pinfunction "SCK_18") (pintype "bidirectional"))
    )
    (net (code "34") (name "Net-(C3-Pad1)") (class "Default")
      (node (ref "C3") (pin "1") (pinfunction "1_1") (pintype "passive"))
      (node (ref "U$10") (pin "2") (pinfunction "2_2") (pintype "bidirectional"))
      (node (ref "U$12") (pin "1") (pinfunction "1_1") (pintype "bidirectional"))
      (node (ref "U$16") (pin "2") (pinfunction "2_2") (pintype "bidirectional"))
    )
    (net (code "35") (name "Net-(C3-Pad2)") (class "Default")
      (node (ref "C3") (pin "2") (pinfunction "2_2") (pintype "passive"))
      (node (ref "C37") (pin "1") (pinfunction "1_1") (pintype "passive"))
      (node (ref "C38") (pin "1") (pinfunction "1_1") (pintype "passive"))
      (node (ref "U$12") (pin "2") (pinfunction "2_2") (pintype "bidirectional"))
    )
    (net (code "36") (name "Net-(C38-Pad2)") (class "Default")
      (node (ref "C38") (pin "2") (pinfunction "2_2") (pintype "passive"))
      (node (ref "U$13") (pin "1") (pinfunction "1_1") (pintype "bidirectional"))
    )
    (net (code "37") (name "Net-(C43-Pad2)") (class "Default")
      (node (ref "C43") (pin "2") (pinfunction "2_2") (pintype "passive"))
      (node (ref "C44") (pin "1") (pinfunction "1_1") (pintype "passive"))
      (node (ref "U$15") (pin "1") (pinfunction "1_1") (pintype "bidirectional"))
    )
    (net (code "38") (name "Net-(CR5-22)") (class "Default")
      (node (ref "CR5") (pin "2") (pinfunction "22_2") (pintype "passive"))
      (node (ref "R40") (pin "1") (pinfunction "1_1") (pintype "passive"))
      (node (ref "U$6") (pin "P$3") (pinfunction "D+_P$3") (pintype "bidirectional"))
    )
    (net (code "39") (name "Net-(CR6-22)") (class "Default")
      (node (ref "CR6") (pin "2") (pinfunction "22_2") (pintype "passive"))
      (node (ref "R39") (pin "1") (pinfunction "1_1") (pintype "passive"))
      (node (ref "U$6") (pin "P$2") (pinfunction "D-_P$2") (pintype "bidirectional"))
    )
    (net (code "40") (name "Net-(CR7-22)") (class "Default")
      (node (ref "CR7") (pin "2") (pinfunction "22_2") (pintype "passive"))
      (node (ref "J7") (pin "2") (pinfunction "D-_2") (pintype "bidirectional"))
      (node (ref "U$1") (pin "44") (pinfunction "PA11_44") (pintype "bidirectional"))
    )
    (net (code "41") (name "Net-(CR8-22)") (class "Default")
      (node (ref "CR8") (pin "2") (pinfunction "22_2") (pintype "passive"))
      (node (ref "J7") (pin "3") (pinfunction "D+_3") (pintype "bidirectional"))
      (node (ref "U$1") (pin "45") (pinfunction "PA12_45") (pintype "bidirectional"))
    )
    (net (code "42") (name "Net-(J5-+)") (class "Default")
      (node (ref "J5") (pin "2") (pinfunction "+_2") (pintype "bidirectional"))
      (node (ref "U$17") (pin "2") (pinfunction "2_2") (pintype "bidirectional"))
    )
    (net (code "43") (name "Net-(LED1-PadC)") (class "Default")
      (node (ref "LED1") (pin "C") (pinfunction "C_C") (pintype "passive"))
      (node (ref "R1") (pin "1") (pinfunction "1_1") (pintype "passive"))
    )
    (net (code "44") (name "Net-(LED2-PadC)") (class "Default")
      (node (ref "LED2") (pin "C") (pinfunction "C_C") (pintype "passive"))
      (node (ref "R34") (pin "1") (pinfunction "1_1") (pintype "passive"))
    )
    (net (code "45") (name "Net-(LED3-PadC)") (class "Default")
      (node (ref "LED3") (pin "C") (pinfunction "C_C") (pintype "passive"))
      (node (ref "R35") (pin "1") (pinfunction "1_1") (pintype "passive"))
    )
    (net (code "46") (name "Net-(LED4-PadC)") (class "Default")
      (node (ref "LED4") (pin "C") (pinfunction "C_C") (pintype "passive"))
      (node (ref "R36") (pin "1") (pinfunction "1_1") (pintype "passive"))
    )
    (net (code "47") (name "Net-(LED5-PadA)") (class "Default")
      (node (ref "LED5") (pin "A") (pinfunction "A_A") (pintype "passive"))
      (node (ref "R14") (pin "1") (pinfunction "1_1") (pintype "passive"))
    )
    (net (code "48") (name "Net-(LED6-PadA)") (class "Default")
      (node (ref "LED6") (pin "A") (pinfunction "A_A") (pintype "passive"))
      (node (ref "R16") (pin "1") (pinfunction "1_1") (pintype "passive"))
    )
    (net (code "49") (name "Net-(LED7-PadA)") (class "Default")
      (node (ref "LED7") (pin "A") (pinfunction "A_A") (pintype "passive"))
      (node (ref "R20") (pin "1") (pinfunction "1_1") (pintype "passive"))
    )
    (net (code "50") (name "Net-(LED8-PadA)") (class "Default")
      (node (ref "LED8") (pin "A") (pinfunction "A_A") (pintype "passive"))
      (node (ref "R22") (pin "1") (pinfunction "1_1") (pintype "passive"))
    )
    (net (code "51") (name "Net-(LED9-PadA)") (class "Default")
      (node (ref "LED9") (pin "A") (pinfunction "A_A") (pintype "passive"))
      (node (ref "R24") (pin "1") (pinfunction "1_1") (pintype "passive"))
    )
    (net (code "52") (name "Net-(LED10-PadA)") (class "Default")
      (node (ref "LED10") (pin "A") (pinfunction "A_A") (pintype "passive"))
      (node (ref "R37") (pin "1") (pinfunction "1_1") (pintype "passive"))
    )
    (net (code "53") (name "Net-(LED11-PadA)") (class "Default")
      (node (ref "LED11") (pin "A") (pinfunction "A_A") (pintype "passive"))
      (node (ref "R38") (pin "1") (pinfunction "1_1") (pintype "passive"))
    )
    (net (code "54") (name "Net-(LED12-PadA)") (class "Default")
      (node (ref "LED12") (pin "A") (pinfunction "A_A") (pintype "passive"))
      (node (ref "R26") (pin "1") (pinfunction "1_1") (pintype "passive"))
    )
    (net (code "55") (name "Net-(LED13-PadA)") (class "Default")
      (node (ref "LED13") (pin "A") (pinfunction "A_A") (pintype "passive"))
      (node (ref "R41") (pin "1") (pinfunction "1_1") (pintype "passive"))
    )
    (net (code "56") (name "Net-(LED14-PadA)") (class "Default")
      (node (ref "LED14") (pin "A") (pinfunction "A_A") (pintype "passive"))
      (node (ref "R42") (pin "1") (pinfunction "1_1") (pintype "passive"))
    )
    (net (code "57") (name "Net-(LED15-PadA)") (class "Default")
      (node (ref "LED15") (pin "A") (pinfunction "A_A") (pintype "passive"))
      (node (ref "R43") (pin "1") (pinfunction "1_1") (pintype "passive"))
    )
    (net (code "58") (name "Net-(Q1-S)") (class "Default")
      (node (ref "Q1") (pin "2") (pinfunction "S_2") (pintype "bidirectional"))
      (node (ref "U6") (pin "18") (pinfunction "RESET_N_18") (pintype "bidirectional"))
    )
    (net (code "59") (name "Net-(U$1-PA8)") (class "Default")
      (node (ref "LED4") (pin "A") (pinfunction "A_A") (pintype "passive"))
      (node (ref "U$1") (pin "41") (pinfunction "PA8_41") (pintype "bidirectional"))
    )
    (net (code "60") (name "Net-(U$1-PB1)") (class "Default")
      (node (ref "S5") (pin "P$3") (pinfunction "P$3_P$3") (pintype "bidirectional"))
      (node (ref "U$1") (pin "27") (pinfunction "PB1_27") (pintype "bidirectional"))
    )
    (net (code "61") (name "Net-(U$1-PB2)") (class "Default")
      (node (ref "S4") (pin "P$3") (pinfunction "P$3_P$3") (pintype "bidirectional"))
      (node (ref "U$1") (pin "28") (pinfunction "PB2_28") (pintype "bidirectional"))
    )
    (net (code "62") (name "Net-(U$1-PB10)") (class "Default")
      (node (ref "S3") (pin "P$3") (pinfunction "P$3_P$3") (pintype "bidirectional"))
      (node (ref "U$1") (pin "29") (pinfunction "PB10_29") (pintype "bidirectional"))
    )
    (net (code "63") (name "Net-(U$1-PB11)") (class "Default")
      (node (ref "S2") (pin "P$3") (pinfunction "P$3_P$3") (pintype "bidirectional"))
      (node (ref "U$1") (pin "30") (pinfunction "PB11_30") (pintype "bidirectional"))
    )
    (net (code "64") (name "Net-(U$1-PC7)") (class "Default")
      (node (ref "LED1") (pin "A") (pinfunction "A_A") (pintype "passive"))
      (node (ref "U$1") (pin "38") (pinfunction "PC7_38") (pintype "bidirectional"))
    )
    (net (code "65") (name "Net-(U$1-PC8)") (class "Default")
      (node (ref "LED2") (pin "A") (pinfunction "A_A") (pintype "passive"))
      (node (ref "U$1") (pin "39") (pinfunction "PC8_39") (pintype "bidirectional"))
    )
    (net (code "66") (name "Net-(U$1-PC9)") (class "Default")
      (node (ref "LED3") (pin "A") (pinfunction "A_A") (pintype "passive"))
      (node (ref "U$1") (pin "40") (pinfunction "PC9_40") (pintype "bidirectional"))
    )
    (net (code "67") (name "Net-(U$1-PH3-BOOT0)") (class "Default")
      (node (ref "R2") (pin "1") (pinfunction "1_1") (pintype "passive"))
      (node (ref "U$1") (pin "60") (pinfunction "PH3-BOOT0_60") (pintype "bidirectional"))
    )
    (net (code "68") (name "Net-(U$1-VBAT)") (class "Default")
      (node (ref "SJ16") (pin "2") (pinfunction "2_2") (pintype "passive"))
      (node (ref "U$1") (pin "1") (pinfunction "VBAT_1") (pintype "bidirectional"))
    )
    (net (code "69") (name "Net-(U$1-VDDA{slash}VREF+)") (class "Default")
      (node (ref "SJ18") (pin "2") (pinfunction "2_2") (pintype "passive"))
      (node (ref "U$1") (pin "13") (pinfunction "VDDA/VREF+_13") (pintype "bidirectional"))
    )
    (net (code "70") (name "Net-(U$1-VSSA{slash}VREF-)") (class "Default")
      (node (ref "SJ17") (pin "2") (pinfunction "2_2") (pintype "passive"))
      (node (ref "U$1") (pin "12") (pinfunction "VSSA/VREF-_12") (pintype "bidirectional"))
    )
    (net (code "71") (name "Net-(U$2-IN)") (class "Default")
      (node (ref "U$2") (pin "P$1") (pinfunction "IN_P$1") (pintype "bidirectional"))
      (node (ref "X3") (pin "P") (pinfunction "ANT_P") (pintype "bidirectional"))
    )
    (net (code "72") (name "Net-(U$6-VCC)") (class "Default")
      (node (ref "U$6") (pin "P$1") (pinfunction "VCC_P$1") (pintype "bidirectional"))
      (node (ref "U6") (pin "17") (pinfunction "VUSB_DET_17") (pintype "bidirectional"))
    )
    (net (code "73") (name "Net-(U$7-DCC_SW)") (class "Default")
      (node (ref "U$3") (pin "1") (pinfunction "1_1") (pintype "bidirectional"))
      (node (ref "U$7") (pin "9") (pinfunction "DCC_SW_9") (pintype "bidirectional"))
    )
    (net (code "74") (name "Net-(U$7-RFI_N)") (class "Default")
      (node (ref "C40") (pin "1") (pinfunction "1_1") (pintype "passive"))
      (node (ref "U$14") (pin "2") (pinfunction "2_2") (pintype "bidirectional"))
      (node (ref "U$7") (pin "22") (pinfunction "RFI_N_22") (pintype "bidirectional"))
    )
    (net (code "75") (name "Net-(U$7-RFI_P)") (class "Default")
      (node (ref "C42") (pin "1") (pinfunction "1_1") (pintype "passive"))
      (node (ref "U$14") (pin "1") (pinfunction "1_1") (pintype "bidirectional"))
      (node (ref "U$7") (pin "21") (pinfunction "RFI_P_21") (pintype "bidirectional"))
    )
    (net (code "76") (name "Net-(U$7-RFO)") (class "Default")
      (node (ref "U$16") (pin "1") (pinfunction "1_1") (pintype "bidirectional"))
      (node (ref "U$7") (pin "23") (pinfunction "RFO_23") (pintype "bidirectional"))
    )
    (net (code "77") (name "Net-(U$7-VREG)") (class "Default")
      (node (ref "C48") (pin "2") (pinfunction "2_2") (pintype "passive"))
      (node (ref "U$3") (pin "2") (pinfunction "2_2") (pintype "bidirectional"))
      (node (ref "U$7") (pin "7") (pinfunction "VREG_7") (pintype "bidirectional"))
    )
    (net (code "78") (name "Net-(U$7-VR_PA)") (class "Default")
      (node (ref "C1") (pin "1") (pinfunction "1_1") (pintype "passive"))
      (node (ref "C2") (pin "1") (pinfunction "1_1") (pintype "passive"))
      (node (ref "U$10") (pin "1") (pinfunction "1_1") (pintype "bidirectional"))
      (node (ref "U$7") (pin "24") (pinfunction "VR_PA_24") (pintype "bidirectional"))
    )
    (net (code "79") (name "Net-(U$7-XTA)") (class "Default")
      (node (ref "C16") (pin "1") (pinfunction "1_1") (pintype "passive"))
      (node (ref "U$7") (pin "3") (pinfunction "XTA_3") (pintype "bidirectional"))
      (node (ref "Y1") (pin "1") (pinfunction "1_1") (pintype "passive"))
    )
    (net (code "80") (name "Net-(U$7-XTB)") (class "Default")
      (node (ref "C18") (pin "1") (pinfunction "1_1") (pintype "passive"))
      (node (ref "U$7") (pin "4") (pinfunction "XTB_4") (pintype "bidirectional"))
      (node (ref "Y1") (pin "3") (pinfunction "2_3") (pintype "passive"))
    )
    (net (code "81") (name "Net-(U$8-RXD)") (class "Default")
      (node (ref "SJ2") (pin "2") (pinfunction "2_2") (pintype "passive"))
      (node (ref "U$8") (pin "P$3") (pinfunction "RXD_P$3") (pintype "bidirectional"))
    )
    (net (code "82") (name "Net-(U$8-SCL)") (class "Default")
      (node (ref "SJ8") (pin "1") (pinfunction "1_1") (pintype "passive"))
      (node (ref "U$8") (pin "P$17") (pinfunction "SCL_P$17") (pintype "bidirectional"))
    )
    (net (code "83") (name "Net-(U$8-SDA)") (class "Default")
      (node (ref "SJ9") (pin "1") (pinfunction "1_1") (pintype "passive"))
      (node (ref "U$8") (pin "P$16") (pinfunction "SDA_P$16") (pintype "bidirectional"))
    )
    (net (code "84") (name "Net-(U$8-TXD)") (class "Default")
      (node (ref "SJ1") (pin "2") (pinfunction "2_2") (pintype "passive"))
      (node (ref "U$8") (pin "P$2") (pinfunction "TXD_P$2") (pintype "bidirectional"))
    )
    (net (code "85") (name "Net-(U$9-CTRL)") (class "Default")
      (node (ref "C21") (pin "1") (pinfunction "1_1") (pintype "passive"))
      (node (ref "R4") (pin "2") (pinfunction "2_2") (pintype "passive"))
      (node (ref "U$9") (pin "P$4") (pinfunction "CTRL_P$4") (pintype "bidirectional"))
    )
    (net (code "86") (name "Net-(U$9-RF1)") (class "Default")
      (node (ref "C40") (pin "2") (pinfunction "2_2") (pintype "passive"))
      (node (ref "C41") (pin "1") (pinfunction "1_1") (pintype "passive"))
      (node (ref "U$9") (pin "P$3") (pinfunction "RF1_P$3") (pintype "bidirectional"))
    )
    (net (code "87") (name "Net-(U$9-RF2)") (class "Default")
      (node (ref "C39") (pin "1") (pinfunction "1_1") (pintype "passive"))
      (node (ref "U$13") (pin "2") (pinfunction "2_2") (pintype "bidirectional"))
      (node (ref "U$9") (pin "P$1") (pinfunction "RF2_P$1") (pintype "bidirectional"))
    )
    (net (code "88") (name "Net-(U$9-RFIN)") (class "Default")
      (node (ref "C43") (pin "1") (pinfunction "1_1") (pintype "passive"))
      (node (ref "U$9") (pin "P$5") (pinfunction "RFIN_P$5") (pintype "bidirectional"))
    )
    (net (code "89") (name "Net-(U$11-IN)") (class "Default")
      (node (ref "U$11") (pin "6") (pinfunction "IN_6") (pintype "bidirectional"))
      (node (ref "U$2") (pin "P$4") (pinfunction "OUT_P$4") (pintype "bidirectional"))
    )
    (net (code "90") (name "Net-(U$11-OUT)") (class "Default")
      (node (ref "U$11") (pin "3") (pinfunction "OUT_3") (pintype "bidirectional"))
      (node (ref "U$8") (pin "P$11") (pinfunction "RF_IN_P$11") (pintype "bidirectional"))
    )
    (net (code "91") (name "Net-(U$11-VCC)") (class "Default")
      (node (ref "U$11") (pin "1") (pinfunction "VCC_1") (pintype "bidirectional"))
      (node (ref "U$8") (pin "P$14") (pinfunction "VCC_RF_P$14") (pintype "bidirectional"))
    )
    (net (code "92") (name "Net-(U1-CT)") (class "Default")
      (node (ref "C15") (pin "1") (pinfunction "1_1") (pintype "passive"))
      (node (ref "U1") (pin "4") (pinfunction "CT_4") (pintype "bidirectional"))
    )
    (net (code "93") (name "Net-(U1-ON)") (class "Default")
      (node (ref "R7") (pin "1") (pinfunction "1_1") (pintype "passive"))
      (node (ref "SJ10") (pin "2") (pinfunction "2_2") (pintype "passive"))
      (node (ref "U1") (pin "3") (pinfunction "ON_3") (pintype "bidirectional"))
    )
    (net (code "94") (name "Net-(U1-QOD)") (class "Default")
      (node (ref "R3") (pin "1") (pinfunction "1_1") (pintype "passive"))
      (node (ref "U1") (pin "5") (pinfunction "QOD_5") (pintype "bidirectional"))
    )
    (net (code "95") (name "Net-(U1-VOUT)") (class "Default")
      (node (ref "C22") (pin "1") (pinfunction "1_1") (pintype "passive"))
      (node (ref "J6") (pin "2") (pinfunction "2_2") (pintype "passive"))
      (node (ref "R3") (pin "2") (pinfunction "2_2") (pintype "passive"))
      (node (ref "U1") (pin "6") (pinfunction "VOUT_6") (pintype "bidirectional"))
    )
    (net (code "96") (name "Net-(U2-DIR1)") (class "Default")
      (node (ref "R5") (pin "1") (pinfunction "1_1") (pintype "passive"))
      (node (ref "U2") (pin "1") (pinfunction "DIR1_1") (pintype "input"))
    )
    (net (code "97") (name "Net-(U2-DIR2)") (class "Default")
      (node (ref "R6") (pin "1") (pinfunction "1_1") (pintype "passive"))
      (node (ref "U2") (pin "2") (pinfunction "DIR2_2") (pintype "input"))
    )
    (net (code "98") (name "Net-(U2-DIR3)") (class "Default")
      (node (ref "R18") (pin "2") (pinfunction "2_2") (pintype "passive"))
      (node (ref "U2") (pin "7") (pinfunction "DIR3_7") (pintype "input"))
    )
    (net (code "99") (name "Net-(U2-DIR4)") (class "Default")
      (node (ref "R19") (pin "2") (pinfunction "2_2") (pintype "passive"))
      (node (ref "U2") (pin "8") (pinfunction "DIR4_8") (pintype "input"))
    )
    (net (code "100") (name "Net-(U3-CT)") (class "Default")
      (node (ref "C19") (pin "1") (pinfunction "1_1") (pintype "passive"))
      (node (ref "U3") (pin "4") (pinfunction "CT_4") (pintype "bidirectional"))
    )
    (net (code "101") (name "Net-(U3-ON)") (class "Default")
      (node (ref "R9") (pin "1") (pinfunction "1_1") (pintype "passive"))
      (node (ref "SJ11") (pin "2") (pinfunction "2_2") (pintype "passive"))
      (node (ref "U3") (pin "3") (pinfunction "ON_3") (pintype "bidirectional"))
    )
    (net (code "102") (name "Net-(U3-QOD)") (class "Default")
      (node (ref "R8") (pin "1") (pinfunction "1_1") (pintype "passive"))
      (node (ref "U3") (pin "5") (pinfunction "QOD_5") (pintype "bidirectional"))
    )
    (net (code "103") (name "Net-(U3-VOUT)") (class "Default")
      (node (ref "C23") (pin "1") (pinfunction "1_1") (pintype "passive"))
      (node (ref "J2") (pin "2") (pinfunction "2_2") (pintype "passive"))
      (node (ref "R8") (pin "2") (pinfunction "2_2") (pintype "passive"))
      (node (ref "U3") (pin "6") (pinfunction "VOUT_6") (pintype "bidirectional"))
    )
    (net (code "104") (name "Net-(U4-CT)") (class "Default")
      (node (ref "C24") (pin "1") (pinfunction "1_1") (pintype "passive"))
      (node (ref "U4") (pin "4") (pinfunction "CT_4") (pintype "bidirectional"))
    )
    (net (code "105") (name "Net-(U4-ON)") (class "Default")
      (node (ref "R28") (pin "1") (pinfunction "1_1") (pintype "passive"))
      (node (ref "SJ12") (pin "2") (pinfunction "2_2") (pintype "passive"))
      (node (ref "U4") (pin "3") (pinfunction "ON_3") (pintype "bidirectional"))
    )
    (net (code "106") (name "Net-(U4-QOD)") (class "Default")
      (node (ref "R12") (pin "1") (pinfunction "1_1") (pintype "passive"))
      (node (ref "U4") (pin "5") (pinfunction "QOD_5") (pintype "bidirectional"))
    )
    (net (code "107") (name "Net-(U4-VOUT)") (class "Default")
      (node (ref "C26") (pin "1") (pinfunction "1_1") (pintype "passive"))
      (node (ref "J3") (pin "2") (pinfunction "2_2") (pintype "passive"))
      (node (ref "R12") (pin "2") (pinfunction "2_2") (pintype "passive"))
      (node (ref "U4") (pin "6") (pinfunction "VOUT_6") (pintype "bidirectional"))
    )
    (net (code "108") (name "Net-(U5-CT)") (class "Default")
      (node (ref "C27") (pin "1") (pinfunction "1_1") (pintype "passive"))
      (node (ref "U5") (pin "4") (pinfunction "CT_4") (pintype "bidirectional"))
    )
    (net (code "109") (name "Net-(U5-ON)") (class "Default")
      (node (ref "R30") (pin "1") (pinfunction "1_1") (pintype "passive"))
      (node (ref "SJ13") (pin "2") (pinfunction "2_2") (pintype "passive"))
      (node (ref "U5") (pin "3") (pinfunction "ON_3") (pintype "bidirectional"))
    )
    (net (code "110") (name "Net-(U5-QOD)") (class "Default")
      (node (ref "R29") (pin "1") (pinfunction "1_1") (pintype "passive"))
      (node (ref "U5") (pin "5") (pinfunction "QOD_5") (pintype "bidirectional"))
    )
    (net (code "111") (name "Net-(U5-VOUT)") (class "Default")
      (node (ref "C29") (pin "1") (pinfunction "1_1") (pintype "passive"))
      (node (ref "J4") (pin "2") (pinfunction "2_2") (pintype "passive"))
      (node (ref "R29") (pin "2") (pinfunction "2_2") (pintype "passive"))
      (node (ref "U5") (pin "6") (pinfunction "VOUT_6") (pintype "bidirectional"))
    )
    (net (code "112") (name "Net-(U6-ANT)") (class "Default")
      (node (ref "U6") (pin "56") (pinfunction "ANT_56") (pintype "bidirectional"))
      (node (ref "X1") (pin "3") (pinfunction "SIGNAL_3") (pintype "passive"))
    )
    (net (code "113") (name "Net-(U6-CTS)") (class "Default")
      (node (ref "SJ5") (pin "2") (pinfunction "2_2") (pintype "passive"))
      (node (ref "U6") (pin "11") (pinfunction "CTS_11") (pintype "bidirectional"))
    )
    (net (code "114") (name "Net-(U6-DTR)") (class "Default")
      (node (ref "SJ3") (pin "2") (pinfunction "2_2") (pintype "passive"))
      (node (ref "U6") (pin "9") (pinfunction "DTR_9") (pintype "bidirectional"))
    )
    (net (code "115") (name "Net-(U6-RTS)") (class "Default")
      (node (ref "SJ4") (pin "2") (pinfunction "2_2") (pintype "passive"))
      (node (ref "U6") (pin "10") (pinfunction "RTS_10") (pintype "bidirectional"))
    )
    (net (code "116") (name "Net-(U6-RXD)") (class "Default")
      (node (ref "SJ7") (pin "2") (pinfunction "2_2") (pintype "passive"))
      (node (ref "U6") (pin "13") (pinfunction "RXD_13") (pintype "bidirectional"))
    )
    (net (code "117") (name "Net-(U6-TXD)") (class "Default")
      (node (ref "SJ6") (pin "2") (pinfunction "2_2") (pintype "passive"))
      (node (ref "U6") (pin "12") (pinfunction "TXD_12") (pintype "bidirectional"))
    )
    (net (code "118") (name "Net-(U6-USB_D+)") (class "Default")
      (node (ref "R40") (pin "2") (pinfunction "2_2") (pintype "passive"))
      (node (ref "U6") (pin "29") (pinfunction "USB_D+_29") (pintype "bidirectional"))
    )
    (net (code "119") (name "Net-(U6-USB_D-)") (class "Default")
      (node (ref "R39") (pin "2") (pinfunction "2_2") (pintype "passive"))
      (node (ref "U6") (pin "28") (pinfunction "USB_D-_28") (pintype "bidirectional"))
    )
    (net (code "120") (name "Net-(U7-D)") (class "Default")
      (node (ref "LED5") (pin "C") (pinfunction "C_C") (pintype "passive"))
      (node (ref "U7") (pin "3") (pinfunction "D_3") (pintype "bidirectional"))
    )
    (net (code "121") (name "Net-(U8-D)") (class "Default")
      (node (ref "LED6") (pin "C") (pinfunction "C_C") (pintype "passive"))
      (node (ref "U8") (pin "3") (pinfunction "D_3") (pintype "bidirectional"))
    )
    (net (code "122") (name "Net-(U9-D)") (class "Default")
      (node (ref "LED7") (pin "C") (pinfunction "C_C") (pintype "passive"))
      (node (ref "U9") (pin "3") (pinfunction "D_3") (pintype "bidirectional"))
    )
    (net (code "123") (name "Net-(U10-D)") (class "Default")
      (node (ref "LED8") (pin "C") (pinfunction "C_C") (pintype "passive"))
      (node (ref "U10") (pin "3") (pinfunction "D_3") (pintype "bidirectional"))
    )
    (net (code "124") (name "Net-(U11-D)") (class "Default")
      (node (ref "LED9") (pin "C") (pinfunction "C_C") (pintype "passive"))
      (node (ref "U11") (pin "3") (pinfunction "D_3") (pintype "bidirectional"))
    )
    (net (code "125") (name "Net-(U12-D)") (class "Default")
      (node (ref "LED12") (pin "C") (pinfunction "C_C") (pintype "passive"))
      (node (ref "U12") (pin "3") (pinfunction "D_3") (pintype "bidirectional"))
    )
    (net (code "126") (name "Net-(U14-PG)") (class "Default")
      (node (ref "R31") (pin "1") (pinfunction "1_1") (pintype "passive"))
      (node (ref "U14") (pin "P$8") (pinfunction "PG_P$8") (pintype "bidirectional"))
    )
    (net (code "127") (name "Net-(U14-SW)") (class "Default")
      (node (ref "U$4") (pin "2") (pinfunction "2_2") (pintype "passive"))
      (node (ref "U14") (pin "P$7") (pinfunction "SW_P$7") (pintype "bidirectional"))
    )
    (net (code "128") (name "Net-(X2-ANT)") (class "Default")
      (node (ref "C45") (pin "1") (pinfunction "1_1") (pintype "passive"))
      (node (ref "U$15") (pin "2") (pinfunction "2_2") (pintype "bidirectional"))
      (node (ref "X2") (pin "P") (pinfunction "ANT_P") (pintype "bidirectional"))
    )
    (net (code "129") (name "PACK+") (class "Default")
      (node (ref "C17") (pin "1") (pinfunction "1_1") (pintype "passive"))
      (node (ref "C30") (pin "1") (pinfunction "1_1") (pintype "passive"))
      (node (ref "R7") (pin "2") (pinfunction "2_2") (pintype "passive"))
      (node (ref "U$17") (pin "1") (pinfunction "1_1") (pintype "bidirectional"))
      (node (ref "U1") (pin "1") (pinfunction "VIN_1") (pintype "bidirectional"))
      (node (ref "U14") (pin "P$2") (pinfunction "VIN_P$2") (pintype "bidirectional"))
      (node (ref "U14") (pin "P$3") (pinfunction "EN_P$3") (pintype "bidirectional"))
    )
    (net (code "130") (name "SARA_CTS") (class "Default")
      (node (ref "SJ5") (pin "1") (pinfunction "1_1") (pintype "passive"))
      (node (ref "U2") (pin "13") (pinfunction "B2_13") (pintype "bidirectional"))
    )
    (net (code "131") (name "SARA_POWER_ON") (class "Default")
      (node (ref "Q2") (pin "2") (pinfunction "S_2") (pintype "bidirectional"))
      (node (ref "U6") (pin "15") (pinfunction "PWR_ON_15") (pintype "bidirectional"))
    )
    (net (code "132") (name "SARA_RTS") (class "Default")
      (node (ref "SJ4") (pin "1") (pinfunction "1_1") (pintype "passive"))
      (node (ref "U2") (pin "14") (pinfunction "B1_14") (pintype "bidirectional"))
    )
    (net (code "133") (name "SARA_RX") (class "Default")
      (node (ref "SJ7") (pin "1") (pinfunction "1_1") (pintype "passive"))
      (node (ref "U2") (pin "11") (pinfunction "B4_11") (pintype "bidirectional"))
    )
    (net (code "134") (name "SARA_TX") (class "Default")
      (node (ref "SJ6") (pin "1") (pinfunction "1_1") (pintype "passive"))
      (node (ref "U2") (pin "12") (pinfunction "B3_12") (pintype "bidirectional"))
    )
    (net (code "135") (name "SD_CS") (class "Default")
      (node (ref "U$1") (pin "33") (pinfunction "PB12_33") (pintype "bidirectional"))
      (node (ref "U$5") (pin "T2") (pinfunction "CD/DAT3_T2") (pintype "bidirectional"))
    )
    (net (code "136") (name "SD_DET") (class "Default")
      (node (ref "R27") (pin "1") (pinfunction "1_1") (pintype "passive"))
      (node (ref "U$1") (pin "22") (pinfunction "PA6_22") (pintype "bidirectional"))
      (node (ref "U$5") (pin "SW") (pinfunction "SD_DET_SW") (pintype "bidirectional"))
    )
    (net (code "137") (name "SD_MISO") (class "Default")
      (node (ref "U$1") (pin "35") (pinfunction "PB14_35") (pintype "bidirectional"))
      (node (ref "U$5") (pin "T7") (pinfunction "DAT0_T7") (pintype "bidirectional"))
    )
    (net (code "138") (name "SD_MOSI") (class "Default")
      (node (ref "U$1") (pin "36") (pinfunction "PB15_36") (pintype "bidirectional"))
      (node (ref "U$5") (pin "T3") (pinfunction "CMD_T3") (pintype "bidirectional"))
    )
    (net (code "139") (name "SD_POWER_EN") (class "Default")
      (node (ref "SJ13") (pin "1") (pinfunction "1_1") (pintype "passive"))
      (node (ref "U$1") (pin "24") (pinfunction "PC4_24") (pintype "bidirectional"))
    )
    (net (code "140") (name "SD_SCK") (class "Default")
      (node (ref "U$1") (pin "34") (pinfunction "PB13_34") (pintype "bidirectional"))
      (node (ref "U$5") (pin "T5") (pinfunction "SDCLK_T5") (pintype "bidirectional"))
    )
    (net (code "141") (name "SIM_CLK") (class "Default")
      (node (ref "C10") (pin "1") (pinfunction "1_1") (pintype "passive"))
      (node (ref "CR3") (pin "2") (pinfunction "22_2") (pintype "passive"))
      (node (ref "U$5") (pin "C3") (pinfunction "SIMCLK_C3") (pintype "bidirectional"))
      (node (ref "U6") (pin "38") (pinfunction "SIM_CLK_38") (pintype "bidirectional"))
    )
    (net (code "142") (name "SIM_IO") (class "Default")
      (node (ref "C11") (pin "1") (pinfunction "1_1") (pintype "passive"))
      (node (ref "CR4") (pin "2") (pinfunction "22_2") (pintype "passive"))
      (node (ref "U$5") (pin "C7") (pinfunction "IO_C7") (pintype "bidirectional"))
      (node (ref "U6") (pin "39") (pinfunction "SIM_IO_39") (pintype "bidirectional"))
    )
    (net (code "143") (name "SIM_RST") (class "Default")
      (node (ref "C8") (pin "1") (pinfunction "1_1") (pintype "passive"))
      (node (ref "CR2") (pin "2") (pinfunction "22_2") (pintype "passive"))
      (node (ref "U$5") (pin "C2") (pinfunction "RST_C2") (pintype "bidirectional"))
      (node (ref "U6") (pin "40") (pinfunction "SIM_RST_40") (pintype "bidirectional"))
    )
    (net (code "144") (name "VSIM") (class "Default")
      (node (ref "C7") (pin "1") (pinfunction "1_1") (pintype "passive"))
      (node (ref "C9") (pin "1") (pinfunction "1_1") (pintype "passive"))
      (node (ref "CR1") (pin "2") (pinfunction "22_2") (pintype "passive"))
      (node (ref "U$5") (pin "C1") (pinfunction "VCC_C1") (pintype "bidirectional"))
      (node (ref "U6") (pin "41") (pinfunction "VSIM_41") (pintype "bidirectional"))
    )
    (net (code "145") (name "V_INT") (class "Default")
      (node (ref "C14") (pin "1") (pinfunction "1_1") (pintype "passive"))
      (node (ref "U2") (pin "15") (pinfunction "VCCB_15") (pintype "power_in"))
      (node (ref "U6") (pin "4") (pinfunction "V_INT_4") (pintype "bidirectional"))
    )
    (net (code "146") (name "unconnected-(J5-PAD1-PadNC1)") (class "Default")
      (node (ref "J5") (pin "NC1") (pinfunction "PAD1_NC1") (pintype "bidirectional"))
    )
    (net (code "147") (name "unconnected-(J5-PAD2-PadNC2)") (class "Default")
      (node (ref "J5") (pin "NC2") (pinfunction "PAD2_NC2") (pintype "bidirectional"))
    )
    (net (code "148") (name "unconnected-(J7-ID-Pad4)") (class "Default")
      (node (ref "J7") (pin "4") (pinfunction "ID_4") (pintype "bidirectional"))
    )
    (net (code "149") (name "unconnected-(J7-VCC-Pad1)") (class "Default")
      (node (ref "J7") (pin "1") (pinfunction "VCC_1") (pintype "bidirectional"))
    )
    (net (code "150") (name "unconnected-(JP2-Pad1)") (class "Default")
      (node (ref "JP2") (pin "1") (pinfunction "1_1") (pintype "passive"))
    )
    (net (code "151") (name "unconnected-(JP4-Pad1)") (class "Default")
      (node (ref "JP4") (pin "1") (pinfunction "1_1") (pintype "passive"))
    )
    (net (code "152") (name "unconnected-(S1-PadP$2)") (class "Default")
      (node (ref "S1") (pin "P$2") (pinfunction "P$2_P$2") (pintype "bidirectional"))
    )
    (net (code "153") (name "unconnected-(S1-PadP$3)") (class "Default")
      (node (ref "S1") (pin "P$3") (pinfunction "P$3_P$3") (pintype "bidirectional"))
    )
    (net (code "154") (name "unconnected-(S2-PadP$2)") (class "Default")
      (node (ref "S2") (pin "P$2") (pinfunction "P$2_P$2") (pintype "bidirectional"))
    )
    (net (code "155") (name "unconnected-(S2-PadP$4)") (class "Default")
      (node (ref "S2") (pin "P$4") (pinfunction "P$4_P$4") (pintype "bidirectional"))
    )
    (net (code "156") (name "unconnected-(S3-PadP$2)") (class "Default")
      (node (ref "S3") (pin "P$2") (pinfunction "P$2_P$2") (pintype "bidirectional"))
    )
    (net (code "157") (name "unconnected-(S3-PadP$4)") (class "Default")
      (node (ref "S3") (pin "P$4") (pinfunction "P$4_P$4") (pintype "bidirectional"))
    )
    (net (code "158") (name "unconnected-(S4-PadP$2)") (class "Default")
      (node (ref "S4") (pin "P$2") (pinfunction "P$2_P$2") (pintype "bidirectional"))
    )
    (net (code "159") (name "unconnected-(S4-PadP$4)") (class "Default")
      (node (ref "S4") (pin "P$4") (pinfunction "P$4_P$4") (pintype "bidirectional"))
    )
    (net (code "160") (name "unconnected-(S5-PadP$2)") (class "Default")
      (node (ref "S5") (pin "P$2") (pinfunction "P$2_P$2") (pintype "bidirectional"))
    )
    (net (code "161") (name "unconnected-(S5-PadP$4)") (class "Default")
      (node (ref "S5") (pin "P$4") (pinfunction "P$4_P$4") (pintype "bidirectional"))
    )
    (net (code "162") (name "unconnected-(U$1-PB7-Pad59)") (class "Default")
      (node (ref "U$1") (pin "59") (pinfunction "PB7_59") (pintype "bidirectional"))
    )
    (net (code "163") (name "unconnected-(U$1-PB8-Pad61)") (class "Default")
      (node (ref "U$1") (pin "61") (pinfunction "PB8_61") (pintype "bidirectional"))
    )
    (net (code "164") (name "unconnected-(U$1-PB9-Pad62)") (class "Default")
      (node (ref "U$1") (pin "62") (pinfunction "PB9_62") (pintype "bidirectional"))
    )
    (net (code "165") (name "unconnected-(U$1-PC3-Pad11)") (class "Default")
      (node (ref "U$1") (pin "11") (pinfunction "PC3_11") (pintype "bidirectional"))
    )
    (net (code "166") (name "unconnected-(U$1-PC6-Pad37)") (class "Default")
      (node (ref "U$1") (pin "37") (pinfunction "PC6_37") (pintype "bidirectional"))
    )
    (net (code "167") (name "unconnected-(U$1-PC10-Pad51)") (class "Default")
      (node (ref "U$1") (pin "51") (pinfunction "PC10_51") (pintype "bidirectional"))
    )
    (net (code "168") (name "unconnected-(U$1-PC11-Pad52)") (class "Default")
      (node (ref "U$1") (pin "52") (pinfunction "PC11_52") (pintype "bidirectional"))
    )
    (net (code "169") (name "unconnected-(U$1-PC12-Pad53)") (class "Default")
      (node (ref "U$1") (pin "53") (pinfunction "PC12_53") (pintype "bidirectional"))
    )
    (net (code "170") (name "unconnected-(U$1-PC13-Pad2)") (class "Default")
      (node (ref "U$1") (pin "2") (pinfunction "PC13_2") (pintype "bidirectional"))
    )
    (net (code "171") (name "unconnected-(U$1-PC14-OSC32_IN-Pad3)") (class "Default")
      (node (ref "U$1") (pin "3") (pinfunction "PC14-OSC32_IN_3") (pintype "bidirectional"))
    )
    (net (code "172") (name "unconnected-(U$1-PC15-OSC32_OUT-Pad4)") (class "Default")
      (node (ref "U$1") (pin "4") (pinfunction "PC15-OSC32_OUT_4") (pintype "bidirectional"))
    )
    (net (code "173") (name "unconnected-(U$1-PD2-Pad54)") (class "Default")
      (node (ref "U$1") (pin "54") (pinfunction "PD2_54") (pintype "bidirectional"))
    )
    (net (code "174") (name "unconnected-(U$1-PH0-OSC_IN-Pad5)") (class "Default")
      (node (ref "U$1") (pin "5") (pinfunction "PH0-OSC_IN_5") (pintype "bidirectional"))
    )
    (net (code "175") (name "unconnected-(U$1-PH1-OSC_OUT-Pad6)") (class "Default")
      (node (ref "U$1") (pin "6") (pinfunction "PH1-OSC_OUT_6") (pintype "bidirectional"))
    )
    (net (code "176") (name "unconnected-(U$5-DAT1-PadT8)") (class "Default")
      (node (ref "U$5") (pin "T8") (pinfunction "DAT1_T8") (pintype "bidirectional"))
    )
    (net (code "177") (name "unconnected-(U$5-DAT2-PadT1)") (class "Default")
      (node (ref "U$5") (pin "T1") (pinfunction "DAT2_T1") (pintype "bidirectional"))
    )
    (net (code "178") (name "unconnected-(U$5-VPP-PadC6)") (class "Default")
      (node (ref "U$5") (pin "C6") (pinfunction "VPP_C6") (pintype "bidirectional"))
    )
    (net (code "179") (name "unconnected-(U$6-ID-PadP$4)") (class "Default")
      (node (ref "U$6") (pin "P$4") (pinfunction "ID_P$4") (pintype "bidirectional"))
    )
    (net (code "180") (name "unconnected-(U$7-BUSY-Pad14)") (class "Default")
      (node (ref "U$7") (pin "14") (pinfunction "BUSY_14") (pintype "bidirectional"))
    )
    (net (code "181") (name "unconnected-(U$7-DIO1-Pad13)") (class "Default")
      (node (ref "U$7") (pin "13") (pinfunction "DIO1_13") (pintype "bidirectional"))
    )
    (net (code "182") (name "unconnected-(U$7-DIO3-Pad6)") (class "Default")
      (node (ref "U$7") (pin "6") (pinfunction "DIO3_6") (pintype "bidirectional"))
    )
    (net (code "183") (name "unconnected-(U$8-EXTINT-PadP$5)") (class "Default")
      (node (ref "U$8") (pin "P$5") (pinfunction "EXTINT_P$5") (pintype "bidirectional"))
    )
    (net (code "184") (name "unconnected-(U$8-LNA_EN{slash}RSVD-PadP$13)") (class "Default")
      (node (ref "U$8") (pin "P$13") (pinfunction "LNA_EN/RSVD_P$13") (pintype "bidirectional"))
    )
    (net (code "185") (name "unconnected-(U$8-SAFEBOOT_N-PadP$18)") (class "Default")
      (node (ref "U$8") (pin "P$18") (pinfunction "SAFEBOOT_N_P$18") (pintype "bidirectional"))
    )
    (net (code "186") (name "unconnected-(U$8-TIMEPULSE-PadP$4)") (class "Default")
      (node (ref "U$8") (pin "P$4") (pinfunction "TIMEPULSE_P$4") (pintype "bidirectional"))
    )
    (net (code "187") (name "unconnected-(U$8-V_ANT{slash}RSVD-PadP$15)") (class "Default")
      (node (ref "U$8") (pin "P$15") (pinfunction "V_ANT/RSVD_P$15") (pintype "bidirectional"))
    )
    (net (code "188") (name "unconnected-(U$8-V_BCKP-PadP$6)") (class "Default")
      (node (ref "U$8") (pin "P$6") (pinfunction "V_BCKP_P$6") (pintype "bidirectional"))
    )
    (net (code "189") (name "unconnected-(U$17-Pad3)") (class "Default")
      (node (ref "U$17") (pin "3") (pinfunction "3_3") (pintype "bidirectional"))
    )
    (net (code "190") (name "unconnected-(U6-ANT_DET-Pad62)") (class "Default")
      (node (ref "U6") (pin "62") (pinfunction "ANT_DET_62") (pintype "bidirectional"))
    )
    (net (code "191") (name "unconnected-(U6-DCD-Pad8)") (class "Default")
      (node (ref "U6") (pin "8") (pinfunction "DCD_8") (pintype "bidirectional"))
    )
    (net (code "192") (name "unconnected-(U6-DSR-Pad6)") (class "Default")
      (node (ref "U6") (pin "6") (pinfunction "DSR_6") (pintype "bidirectional"))
    )
    (net (code "193") (name "unconnected-(U6-I2S_CLK{slash}CLK-Pad36)") (class "Default")
      (node (ref "U6") (pin "36") (pinfunction "I2S_CLK/CLK_36") (pintype "bidirectional"))
    )
    (net (code "194") (name "unconnected-(U6-I2S_RXD{slash}MISO-Pad37)") (class "Default")
      (node (ref "U6") (pin "37") (pinfunction "I2S_RXD/MISO_37") (pintype "bidirectional"))
    )
    (net (code "195") (name "unconnected-(U6-I2S_TXD{slash}CS-Pad35)") (class "Default")
      (node (ref "U6") (pin "35") (pinfunction "I2S_TXD/CS_35") (pintype "bidirectional"))
    )
    (net (code "196") (name "unconnected-(U6-I2S_WA{slash}MOSI-Pad34)") (class "Default")
      (node (ref "U6") (pin "34") (pinfunction "I2S_WA/MOSI_34") (pintype "bidirectional"))
    )
    (net (code "197") (name "unconnected-(U6-RI-Pad7)") (class "Default")
      (node (ref "U6") (pin "7") (pinfunction "RI_7") (pintype "bidirectional"))
    )
    (net (code "198") (name "unconnected-(U6-SCL-Pad27)") (class "Default")
      (node (ref "U6") (pin "27") (pinfunction "SCL_27") (pintype "bidirectional"))
    )
    (net (code "199") (name "unconnected-(U6-SDA-Pad26)") (class "Default")
      (node (ref "U6") (pin "26") (pinfunction "SDA_26") (pintype "bidirectional"))
    )
    (net (code "200") (name "unconnected-(U6-SDIO_CLK-Pad45)") (class "Default")
      (node (ref "U6") (pin "45") (pinfunction "SDIO_CLK_45") (pintype "bidirectional"))
    )
    (net (code "201") (name "unconnected-(U6-SDIO_CMD-Pad46)") (class "Default")
      (node (ref "U6") (pin "46") (pinfunction "SDIO_CMD_46") (pintype "bidirectional"))
    )
    (net (code "202") (name "unconnected-(U6-SDIO_D0-Pad47)") (class "Default")
      (node (ref "U6") (pin "47") (pinfunction "SDIO_D0_47") (pintype "bidirectional"))
    )
    (net (code "203") (name "unconnected-(U6-SDIO_D1-Pad49)") (class "Default")
      (node (ref "U6") (pin "49") (pinfunction "SDIO_D1_49") (pintype "bidirectional"))
    )
    (net (code "204") (name "unconnected-(U6-SDIO_D2-Pad44)") (class "Default")
      (node (ref "U6") (pin "44") (pinfunction "SDIO_D2_44") (pintype "bidirectional"))
    )
    (net (code "205") (name "unconnected-(U6-SDIO_D3-Pad48)") (class "Default")
      (node (ref "U6") (pin "48") (pinfunction "SDIO_D3_48") (pintype "bidirectional"))
    )
    (net (code "206") (name "~{CELL_RESET}") (class "Default")
      (node (ref "Q1") (pin "1") (pinfunction "G_1") (pintype "bidirectional"))
      (node (ref "R10") (pin "2") (pinfunction "2_2") (pintype "passive"))
      (node (ref "U$1") (pin "21") (pinfunction "PA5_21") (pintype "bidirectional"))
    )
    (net (code "207") (name "~{GPS_RESET}") (class "Default")
      (node (ref "U$1") (pin "10") (pinfunction "PC2_10") (pintype "bidirectional"))
      (node (ref "U$8") (pin "P$9") (pinfunction "RESET_N_P$9") (pintype "bidirectional"))
    )
    (net (code "208") (name "~{LORA_RESET}") (class "Default")
      (node (ref "JP1") (pin "1") (pinfunction "1_1") (pintype "passive"))
      (node (ref "U$1") (pin "58") (pinfunction "PB6_58") (pintype "bidirectional"))
      (node (ref "U$7") (pin "15") (pinfunction "NRESET_15") (pintype "bidirectional"))
    )
  )
)
